# canSlaveV05b.net
KiCad netlist of a schematic drawn in EAGLE
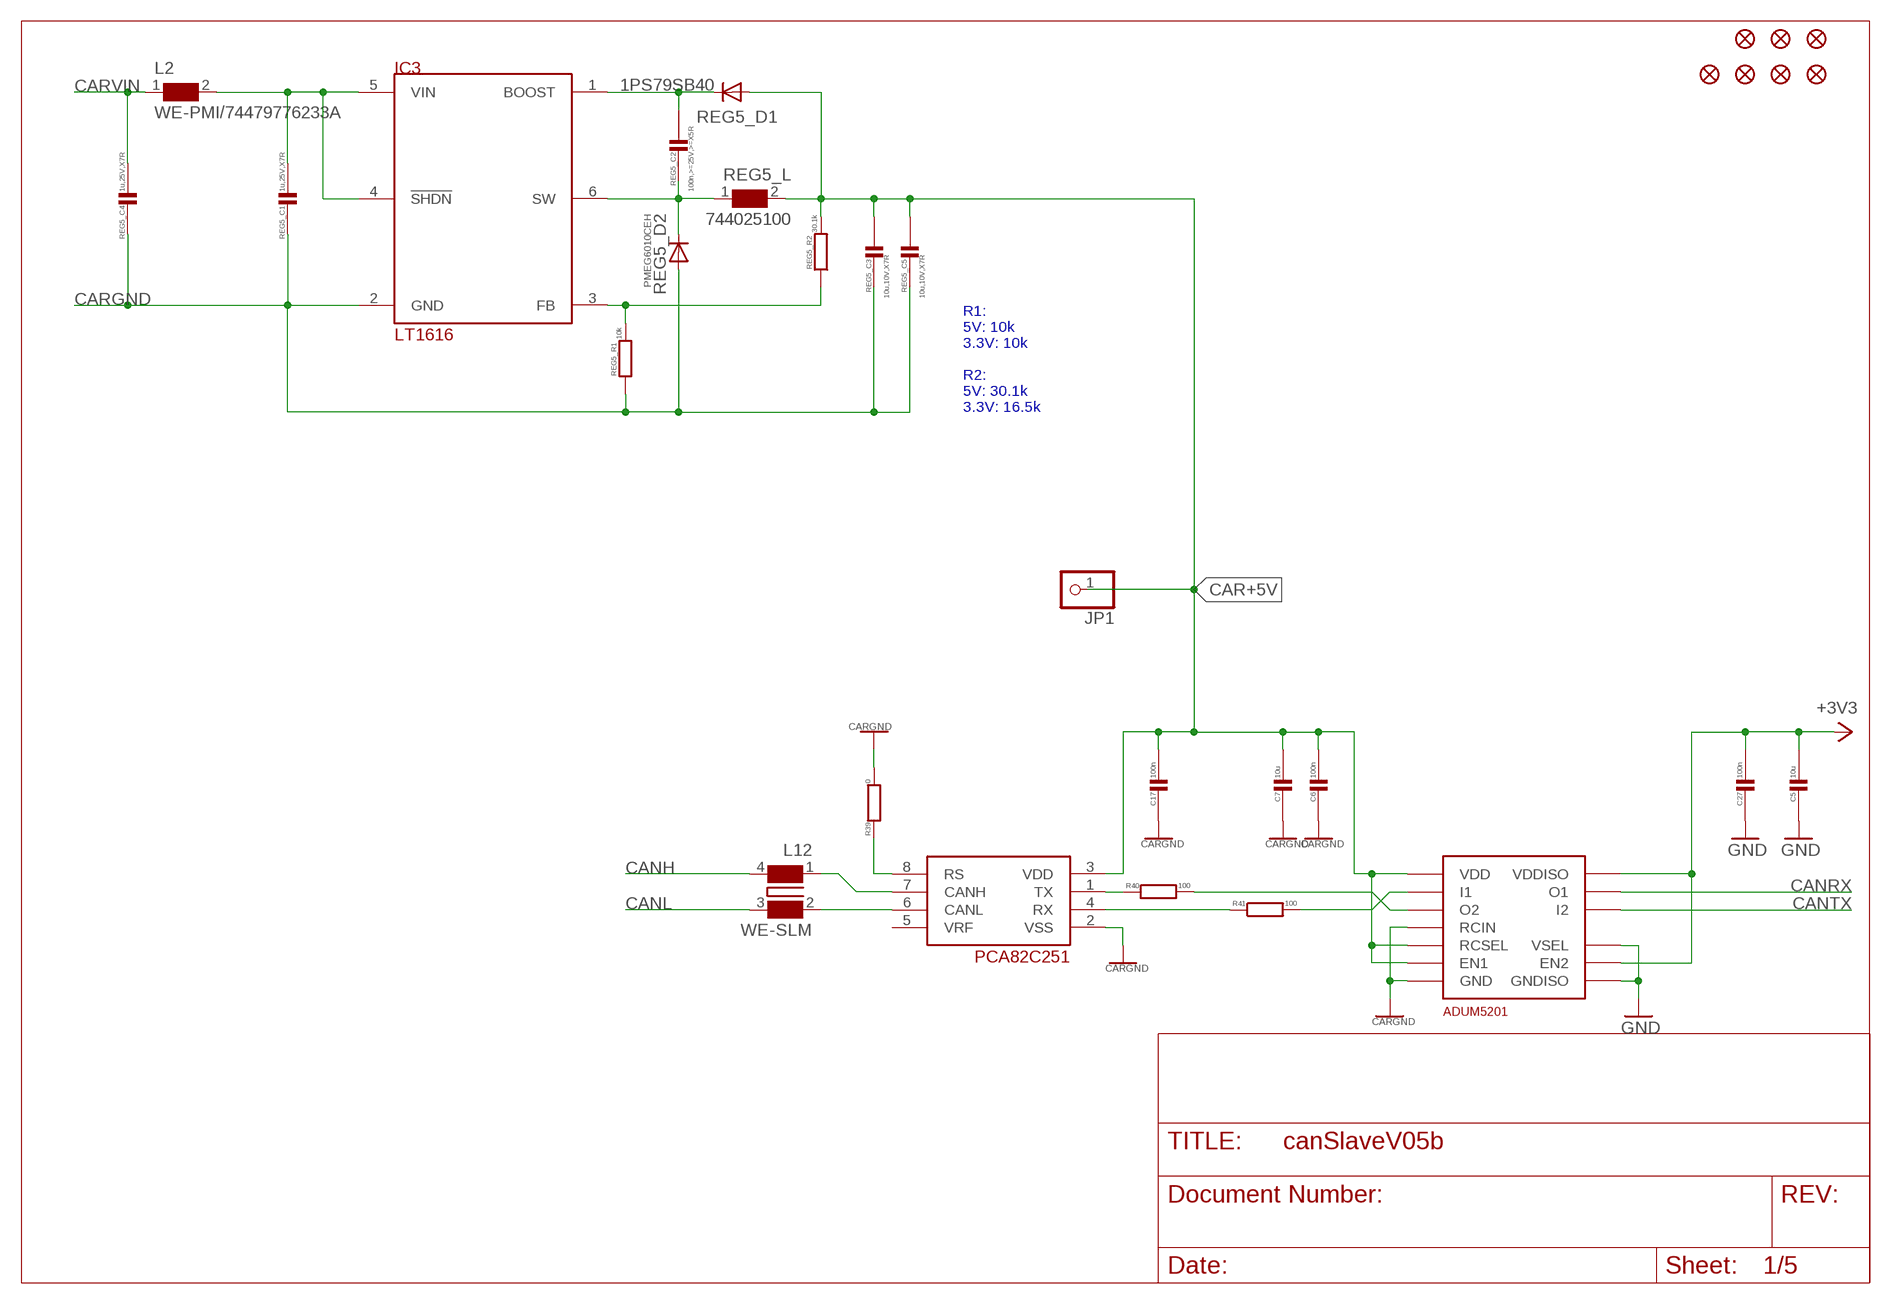
[diagram p0: schematic, sheet 1]
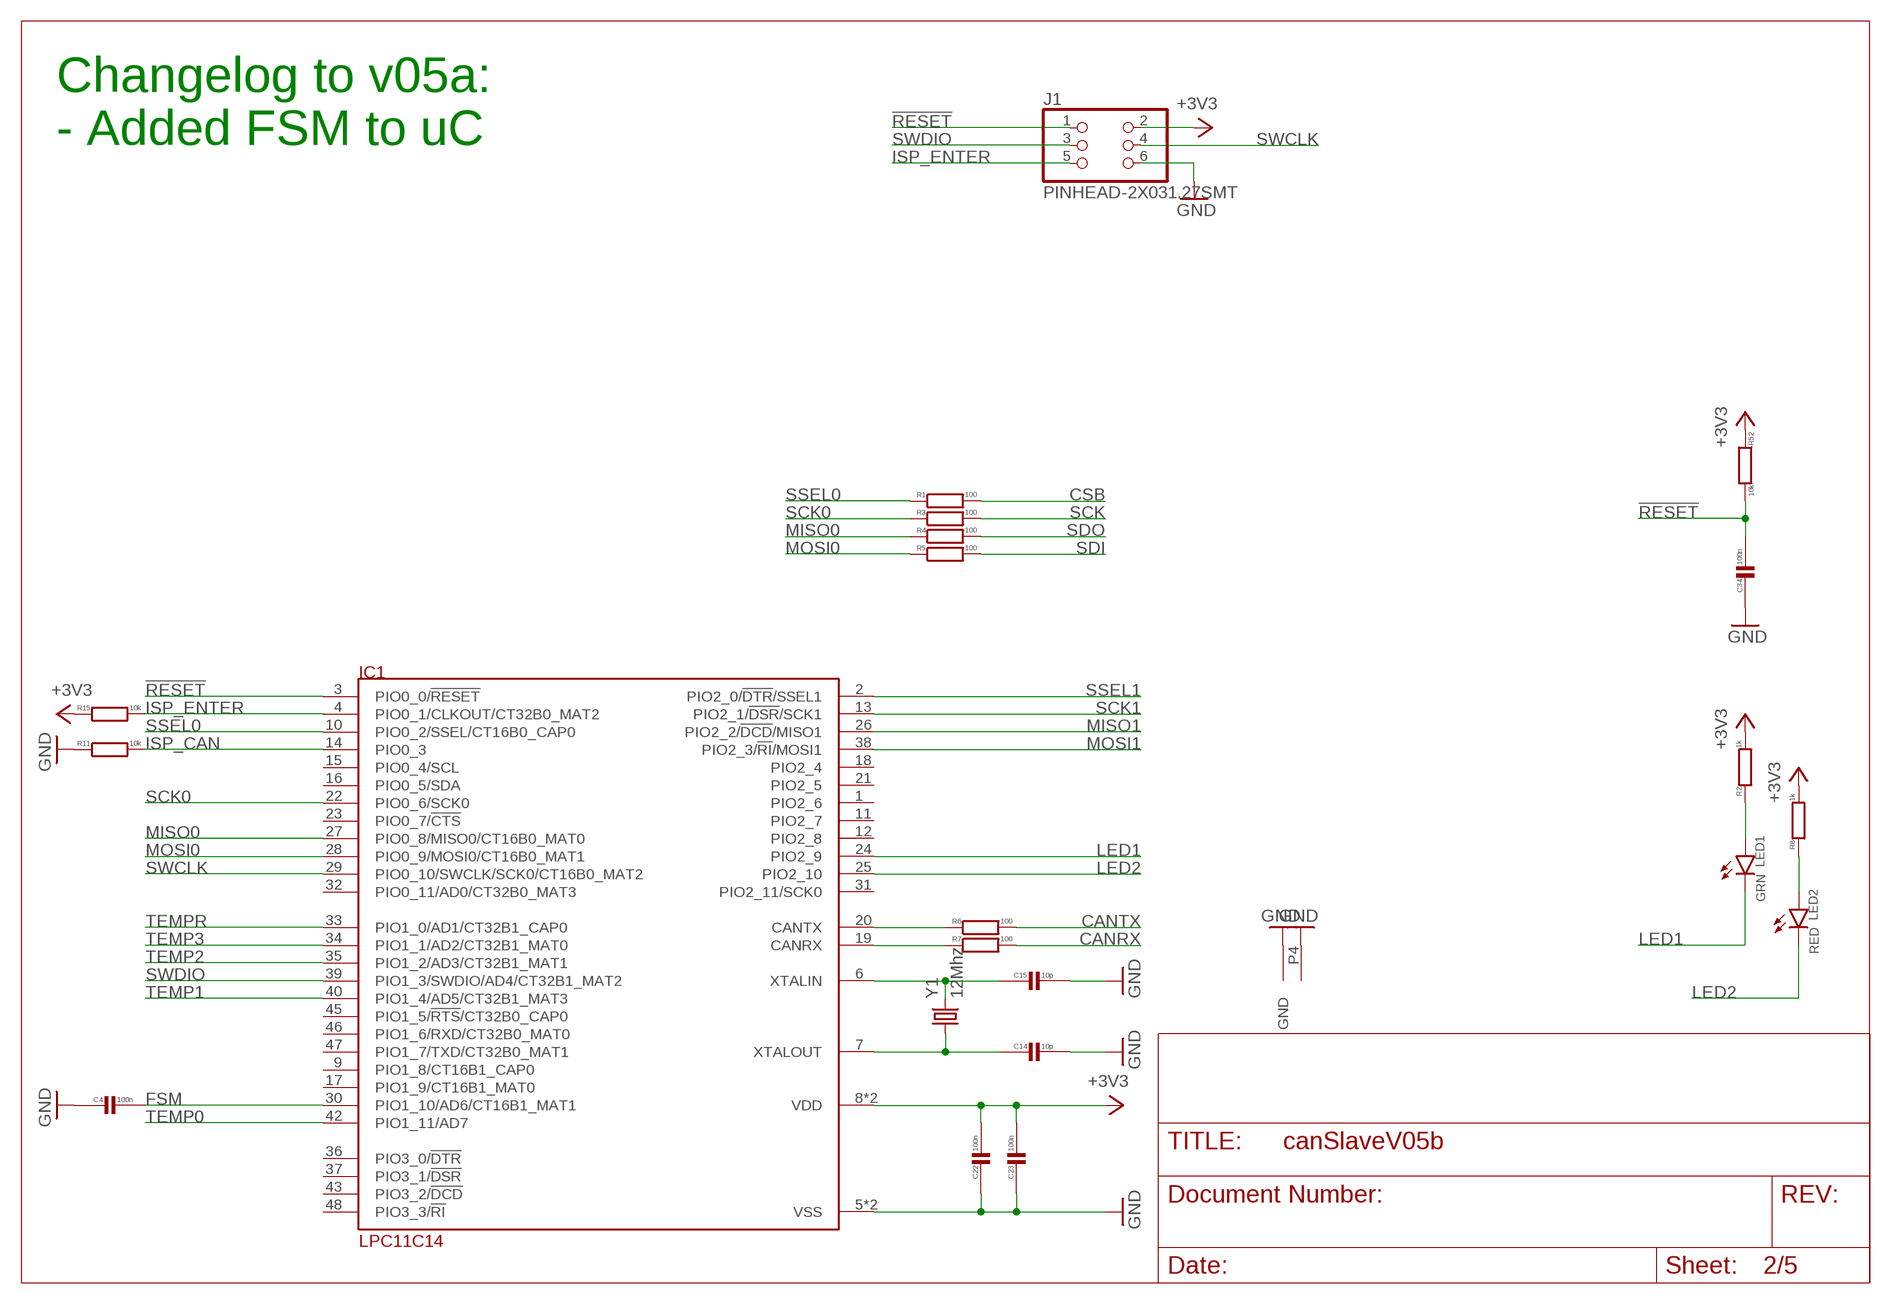
[diagram p1: schematic, sheet 2]
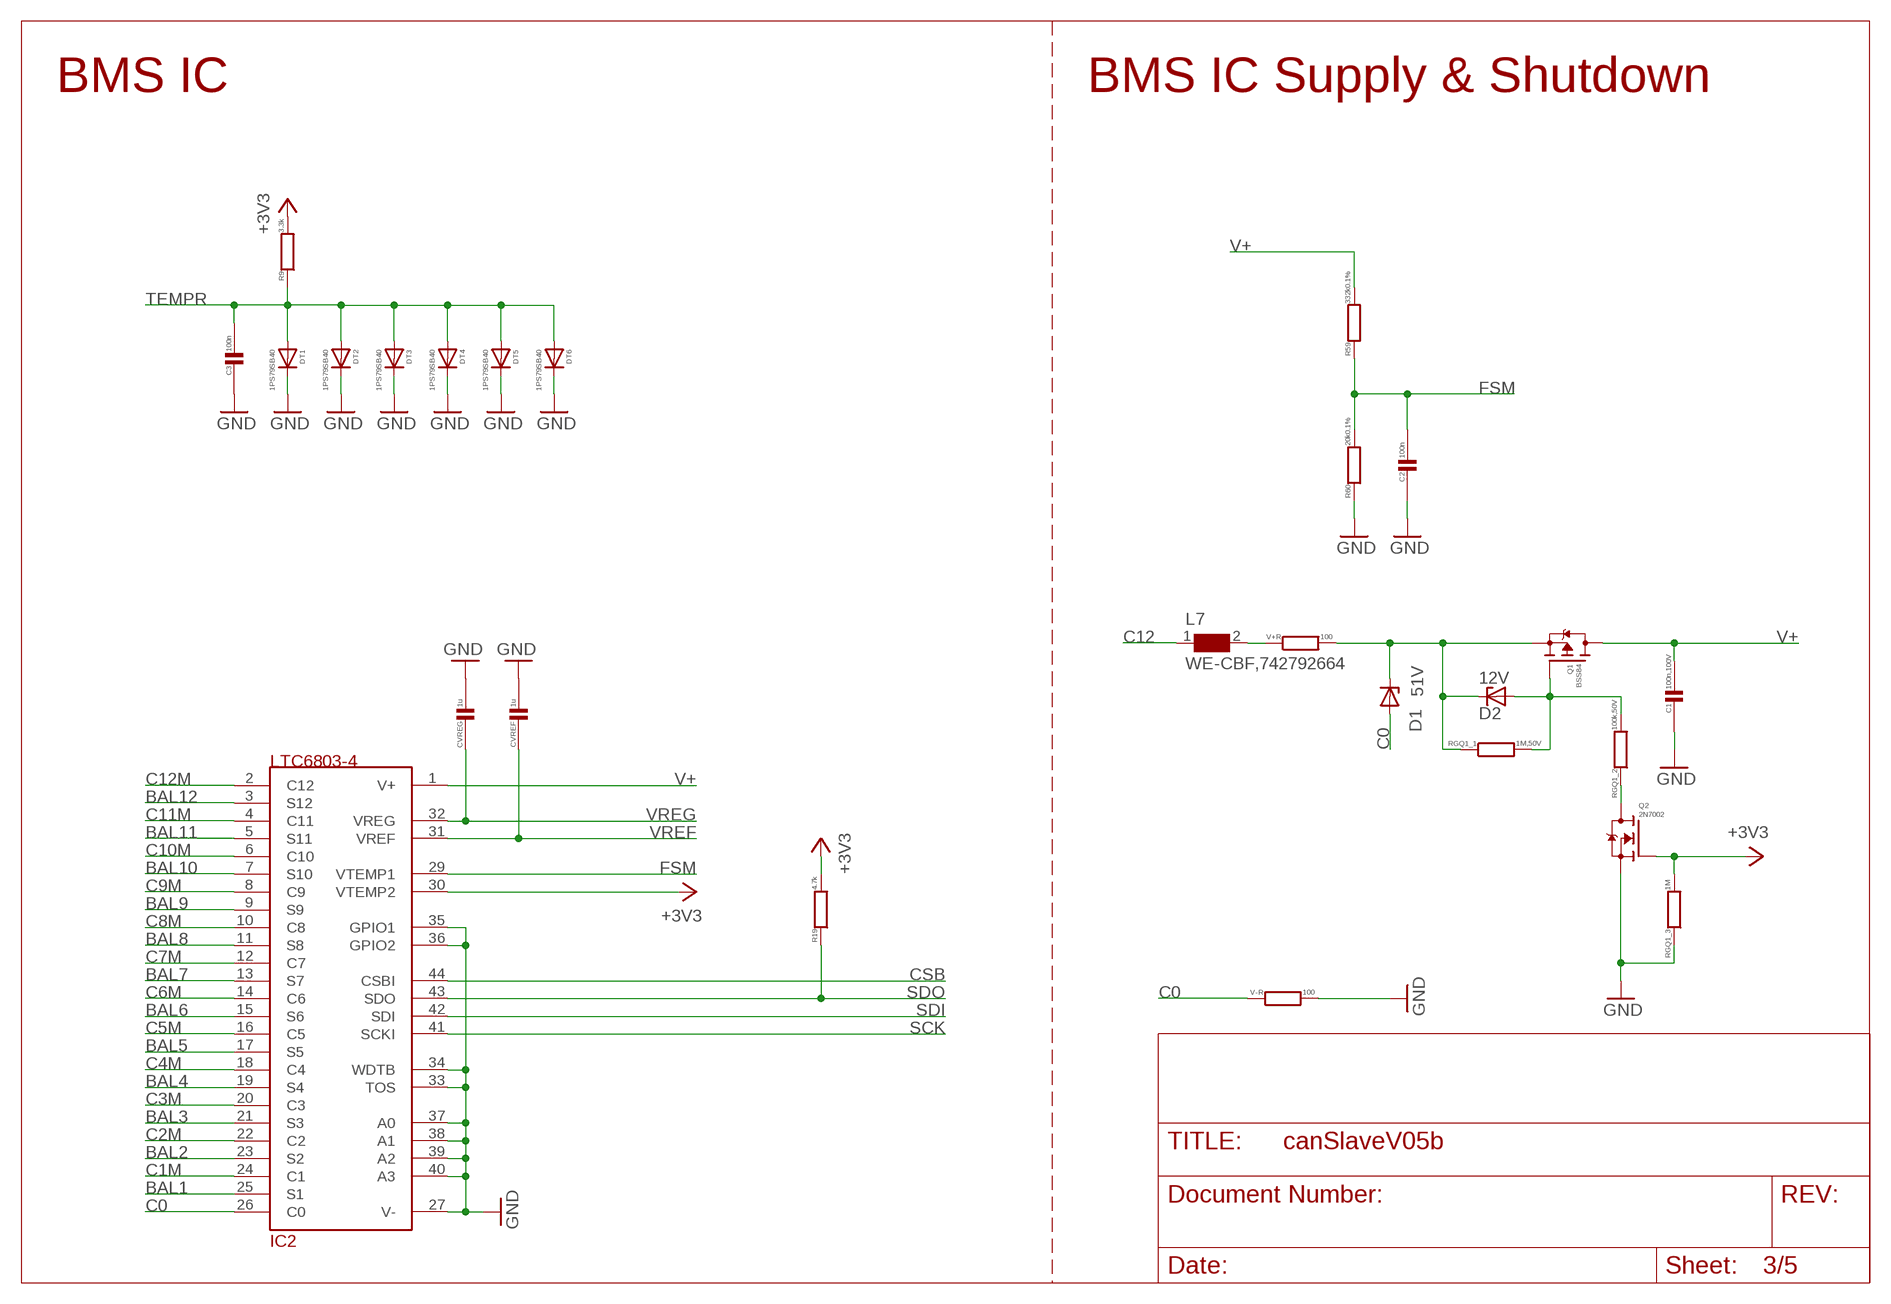
[diagram p2: schematic, sheet 3]
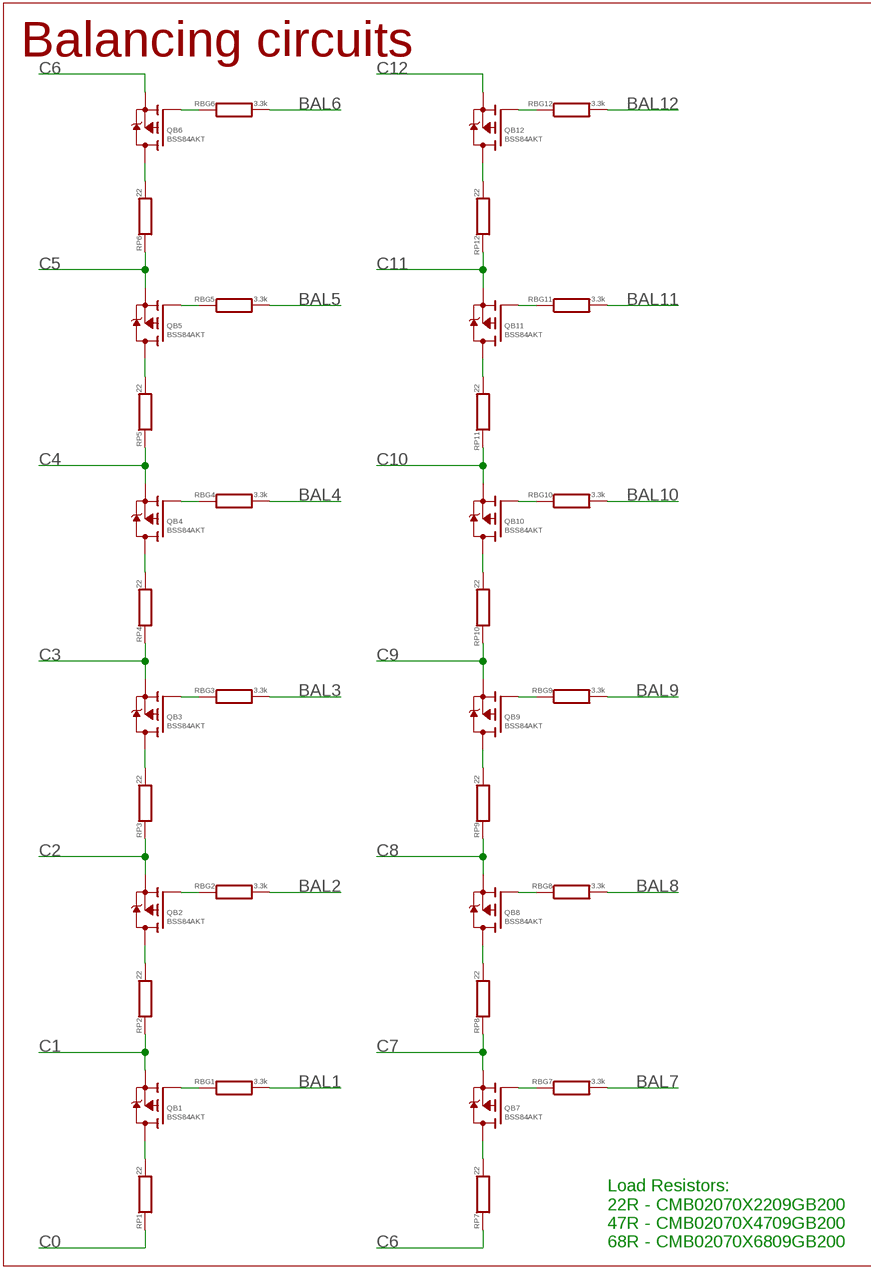
[diagram p3: schematic, sheet 4, part 1 of 2]
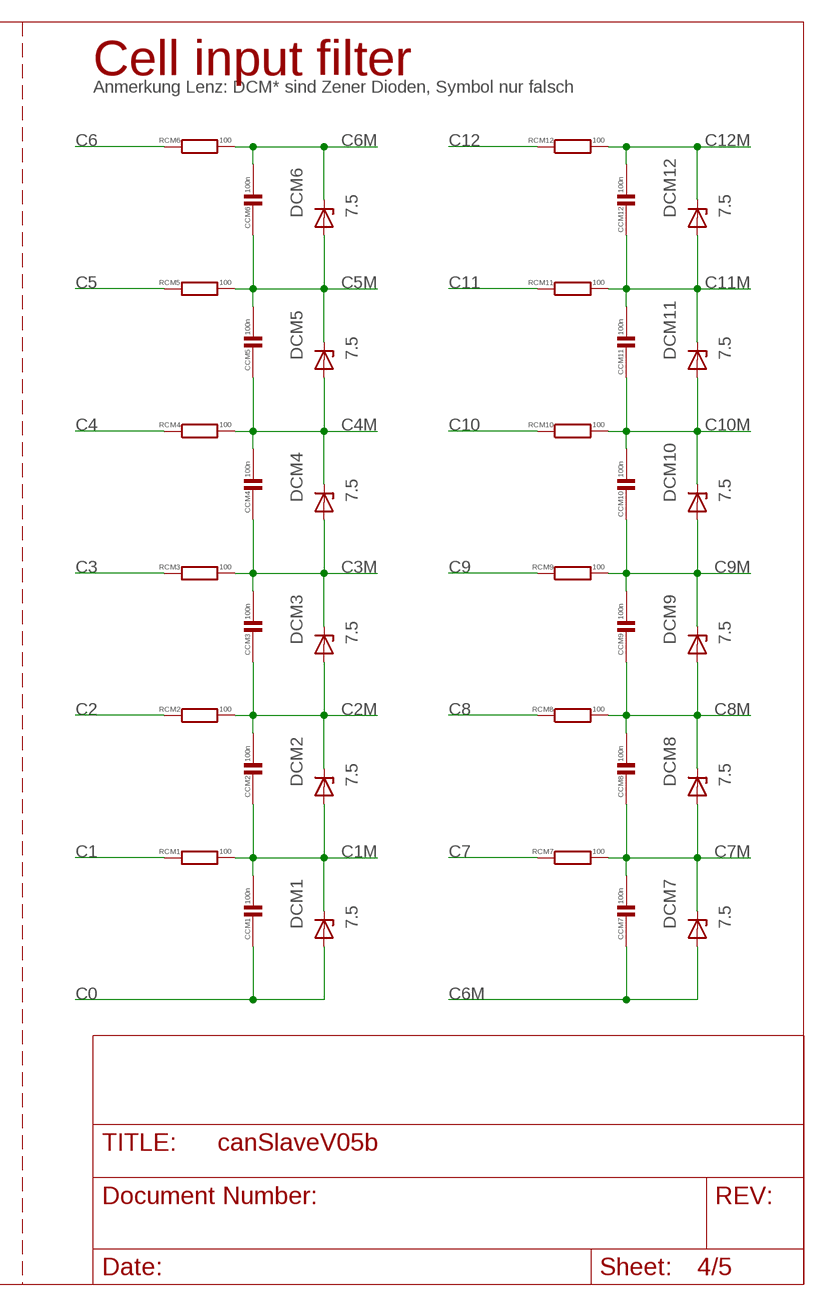
[diagram p4: schematic, sheet 4, part 2 of 2]
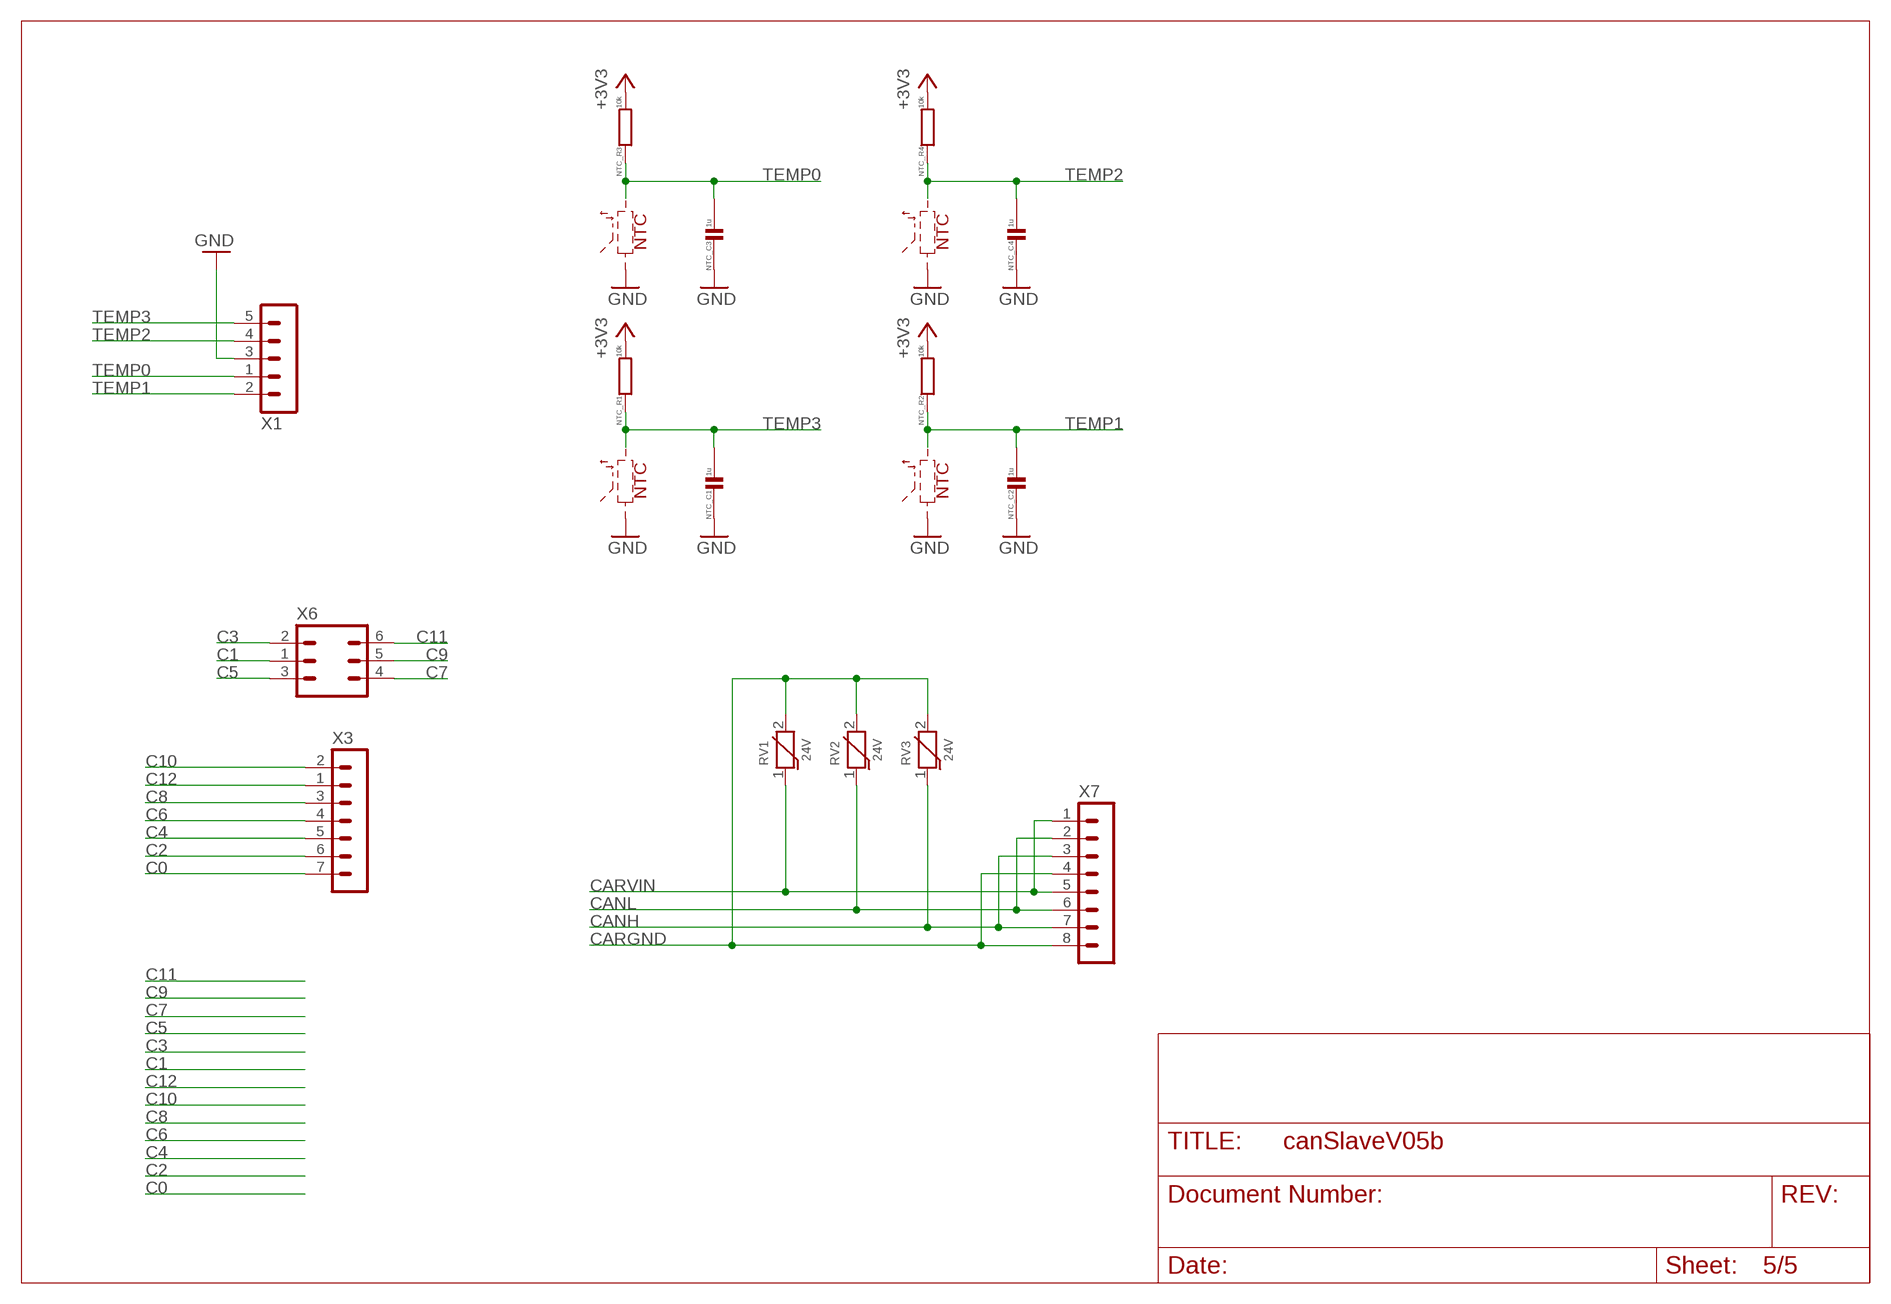
[diagram p5: schematic, sheet 5]

(export (version "E")
  (design (tool "Eeschema 10.0.6"))
  (components
    (comp (ref "NTC_C1")
      (value "1u")
      (footprint "eagle-import:C0402")
      (libsource (lib "eagle-import") (part "C0402"))
    )
    (comp (ref "NTC_C2")
      (value "1u")
      (footprint "eagle-import:C0402")
      (libsource (lib "eagle-import") (part "C0402"))
    )
    (comp (ref "NTC_C3")
      (value "1u")
      (footprint "eagle-import:C0402")
      (libsource (lib "eagle-import") (part "C0402"))
    )
    (comp (ref "NTC_C4")
      (value "1u")
      (footprint "eagle-import:C0402")
      (libsource (lib "eagle-import") (part "C0402"))
    )
    (comp (ref "NTC_R1")
      (value "10k")
      (footprint "eagle-import:R0402")
      (libsource (lib "eagle-import") (part "R0402"))
    )
    (comp (ref "NTC_R2")
      (value "10k")
      (footprint "eagle-import:R0402")
      (libsource (lib "eagle-import") (part "R0402"))
    )
    (comp (ref "NTC_R3")
      (value "10k")
      (footprint "eagle-import:R0402")
      (libsource (lib "eagle-import") (part "R0402"))
    )
    (comp (ref "NTC_R4")
      (value "10k")
      (footprint "eagle-import:R0402")
      (libsource (lib "eagle-import") (part "R0402"))
    )
    (comp (ref "RV1")
      (value "24V")
      (footprint "eagle-import:R0805")
      (libsource (lib "eagle-import") (part "VARISTOR0805"))
    )
    (comp (ref "RV2")
      (value "24V")
      (footprint "eagle-import:R0603")
      (libsource (lib "eagle-import") (part "VARISTOR0603"))
    )
    (comp (ref "RV3")
      (value "24V")
      (footprint "eagle-import:R0603")
      (libsource (lib "eagle-import") (part "VARISTOR0603"))
    )
    (comp (ref "X1")
      (value "HEADER_POS5_43650-0509")
      (footprint "eagle-import:43650-0509")
      (libsource (lib "eagle-import") (part "HEADER_POS5_?43650-0509"))
    )
    (comp (ref "X3")
      (value "HEADER_POS7_43650-0709")
      (footprint "eagle-import:43650-0709")
      (libsource (lib "eagle-import") (part "HEADER_POS7_?43650-0709"))
    )
    (comp (ref "X6")
      (value "HEADER_POS6_43650-0609")
      (footprint "eagle-import:43650-0609")
      (libsource (lib "eagle-import") (part "HEADER_POS6_?43650-0609"))
    )
    (comp (ref "X7")
      (value "HEADER_POS8_43045-0800")
      (footprint "eagle-import:43045-0800")
      (libsource (lib "eagle-import") (part "HEADER_POS8_?43045-0800"))
    )
    (comp (ref "C4")
      (value "100n")
      (footprint "eagle-import:C0402")
      (libsource (lib "eagle-import") (part "C0402"))
    )
    (comp (ref "C14")
      (value "10p")
      (footprint "eagle-import:C0402")
      (libsource (lib "eagle-import") (part "C0402"))
    )
    (comp (ref "C15")
      (value "10p")
      (footprint "eagle-import:C0402")
      (libsource (lib "eagle-import") (part "C0402"))
    )
    (comp (ref "C22")
      (value "100n")
      (footprint "eagle-import:C0402")
      (libsource (lib "eagle-import") (part "C0402"))
    )
    (comp (ref "C23")
      (value "100n")
      (footprint "eagle-import:C0402")
      (libsource (lib "eagle-import") (part "C0402"))
    )
    (comp (ref "C34")
      (value "100n")
      (footprint "eagle-import:C0402")
      (libsource (lib "eagle-import") (part "C0402"))
    )
    (comp (ref "IC1")
      (value "LPC11C14")
      (footprint "eagle-import:LQFP48")
      (libsource (lib "eagle-import") (part "LPC11C1X"))
    )
    (comp (ref "J1")
      (value "PINHEAD-2X031.27SMT")
      (footprint "eagle-import:2X03_1.27MM_SMT")
      (libsource (lib "eagle-import") (part "PINHEAD-2X031.27SMT"))
    )
    (comp (ref "LED1")
      (value "GRN")
      (footprint "eagle-import:CHIPLED_0603")
      (libsource (lib "eagle-import") (part "LED0603"))
    )
    (comp (ref "LED2")
      (value "RED")
      (footprint "eagle-import:CHIPLED_0603")
      (libsource (lib "eagle-import") (part "LED0603"))
    )
    (comp (ref "R1")
      (value "100")
      (footprint "eagle-import:R0402")
      (libsource (lib "eagle-import") (part "R0402"))
    )
    (comp (ref "R2")
      (value "1k")
      (footprint "eagle-import:R0402")
      (libsource (lib "eagle-import") (part "R0402"))
    )
    (comp (ref "R3")
      (value "100")
      (footprint "eagle-import:R0402")
      (libsource (lib "eagle-import") (part "R0402"))
    )
    (comp (ref "R4")
      (value "100")
      (footprint "eagle-import:R0402")
      (libsource (lib "eagle-import") (part "R0402"))
    )
    (comp (ref "R5")
      (value "100")
      (footprint "eagle-import:R0402")
      (libsource (lib "eagle-import") (part "R0402"))
    )
    (comp (ref "R6")
      (value "100")
      (footprint "eagle-import:R0402")
      (libsource (lib "eagle-import") (part "R0402"))
    )
    (comp (ref "R7")
      (value "100")
      (footprint "eagle-import:R0402")
      (libsource (lib "eagle-import") (part "R0402"))
    )
    (comp (ref "R8")
      (value "1k")
      (footprint "eagle-import:R0402")
      (libsource (lib "eagle-import") (part "R0402"))
    )
    (comp (ref "R11")
      (value "10k")
      (footprint "eagle-import:R0402")
      (libsource (lib "eagle-import") (part "R0402"))
    )
    (comp (ref "R15")
      (value "10k")
      (footprint "eagle-import:R0402")
      (libsource (lib "eagle-import") (part "R0402"))
    )
    (comp (ref "R52")
      (value "10k")
      (footprint "eagle-import:R0402")
      (libsource (lib "eagle-import") (part "R0402"))
    )
    (comp (ref "Y1")
      (value "12Mhz")
      (footprint "eagle-import:MT")
      (libsource (lib "eagle-import") (part "CRYSTAL43.2X2.5"))
    )
    (comp (ref "C1")
      (value "100n,100V")
      (footprint "eagle-import:C0603")
      (libsource (lib "eagle-import") (part "C0603"))
    )
    (comp (ref "C2")
      (value "100n")
      (footprint "eagle-import:C0402")
      (libsource (lib "eagle-import") (part "C0402"))
    )
    (comp (ref "C3")
      (value "100n")
      (footprint "eagle-import:C0402")
      (libsource (lib "eagle-import") (part "C0402"))
    )
    (comp (ref "CVREF")
      (value "1u")
      (footprint "eagle-import:C0402")
      (libsource (lib "eagle-import") (part "C0402"))
    )
    (comp (ref "CVREG")
      (value "1u")
      (footprint "eagle-import:C0402")
      (libsource (lib "eagle-import") (part "C0402"))
    )
    (comp (ref "D1")
      (value "51V")
      (footprint "eagle-import:SOD323-L")
      (libsource (lib "eagle-import") (part "ZENERSOD323"))
    )
    (comp (ref "D2")
      (value "12V")
      (footprint "eagle-import:SOD323-L")
      (libsource (lib "eagle-import") (part "ZENERSOD323"))
    )
    (comp (ref "DT1")
      (value "1PS79SB40")
      (footprint "eagle-import:SOD523")
      (libsource (lib "eagle-import") (part "DIODE-SOD523"))
    )
    (comp (ref "DT2")
      (value "1PS79SB40")
      (footprint "eagle-import:SOD523")
      (libsource (lib "eagle-import") (part "DIODE-SOD523"))
    )
    (comp (ref "DT3")
      (value "1PS79SB40")
      (footprint "eagle-import:SOD523")
      (libsource (lib "eagle-import") (part "DIODE-SOD523"))
    )
    (comp (ref "DT4")
      (value "1PS79SB40")
      (footprint "eagle-import:SOD523")
      (libsource (lib "eagle-import") (part "DIODE-SOD523"))
    )
    (comp (ref "DT5")
      (value "1PS79SB40")
      (footprint "eagle-import:SOD523")
      (libsource (lib "eagle-import") (part "DIODE-SOD523"))
    )
    (comp (ref "DT6")
      (value "1PS79SB40")
      (footprint "eagle-import:SOD523")
      (libsource (lib "eagle-import") (part "DIODE-SOD523"))
    )
    (comp (ref "IC2")
      (value "LTC6803-4")
      (footprint "eagle-import:44SSOP")
      (libsource (lib "eagle-import") (part "LTC6803-4"))
    )
    (comp (ref "L7")
      (value "WE-CBF,742792664")
      (footprint "eagle-import:0603")
      (libsource (lib "eagle-import") (part "WE-CBF_0603"))
    )
    (comp (ref "Q1")
      (value "BSS84")
      (footprint "eagle-import:SOT23")
      (libsource (lib "eagle-import") (part "BSS84"))
    )
    (comp (ref "Q2")
      (value "2N7002")
      (footprint "eagle-import:SOT23")
      (libsource (lib "eagle-import") (part "2N7002"))
    )
    (comp (ref "R9")
      (value "3.3k")
      (footprint "eagle-import:R0603")
      (libsource (lib "eagle-import") (part "R0603"))
    )
    (comp (ref "R19")
      (value "4.7k")
      (footprint "eagle-import:R0402")
      (libsource (lib "eagle-import") (part "R0402"))
    )
    (comp (ref "R59")
      (value "332k0.1%")
      (footprint "eagle-import:R0603")
      (libsource (lib "eagle-import") (part "R0603"))
    )
    (comp (ref "R60")
      (value "20k0.1%")
      (footprint "eagle-import:R0402")
      (libsource (lib "eagle-import") (part "R0402"))
    )
    (comp (ref "RGQ1_1")
      (value "1M,50V")
      (footprint "eagle-import:R0603")
      (libsource (lib "eagle-import") (part "R0603"))
    )
    (comp (ref "RGQ1_2")
      (value "100k,50V")
      (footprint "eagle-import:R0603")
      (libsource (lib "eagle-import") (part "R0603"))
    )
    (comp (ref "RGQ1_3")
      (value "1M")
      (footprint "eagle-import:R0402")
      (libsource (lib "eagle-import") (part "R0402"))
    )
    (comp (ref "V+R")
      (value "100")
      (footprint "eagle-import:R0603")
      (libsource (lib "eagle-import") (part "R0603"))
    )
    (comp (ref "V-R")
      (value "100")
      (footprint "eagle-import:R0603")
      (libsource (lib "eagle-import") (part "R0603"))
    )
    (comp (ref "CCM1")
      (value "100n")
      (footprint "eagle-import:C0402")
      (libsource (lib "eagle-import") (part "C0402"))
    )
    (comp (ref "CCM2")
      (value "100n")
      (footprint "eagle-import:C0402")
      (libsource (lib "eagle-import") (part "C0402"))
    )
    (comp (ref "CCM3")
      (value "100n")
      (footprint "eagle-import:C0402")
      (libsource (lib "eagle-import") (part "C0402"))
    )
    (comp (ref "CCM4")
      (value "100n")
      (footprint "eagle-import:C0402")
      (libsource (lib "eagle-import") (part "C0402"))
    )
    (comp (ref "CCM5")
      (value "100n")
      (footprint "eagle-import:C0402")
      (libsource (lib "eagle-import") (part "C0402"))
    )
    (comp (ref "CCM6")
      (value "100n")
      (footprint "eagle-import:C0402")
      (libsource (lib "eagle-import") (part "C0402"))
    )
    (comp (ref "CCM7")
      (value "100n")
      (footprint "eagle-import:C0402")
      (libsource (lib "eagle-import") (part "C0402"))
    )
    (comp (ref "CCM8")
      (value "100n")
      (footprint "eagle-import:C0402")
      (libsource (lib "eagle-import") (part "C0402"))
    )
    (comp (ref "CCM9")
      (value "100n")
      (footprint "eagle-import:C0402")
      (libsource (lib "eagle-import") (part "C0402"))
    )
    (comp (ref "CCM10")
      (value "100n")
      (footprint "eagle-import:C0402")
      (libsource (lib "eagle-import") (part "C0402"))
    )
    (comp (ref "CCM11")
      (value "100n")
      (footprint "eagle-import:C0402")
      (libsource (lib "eagle-import") (part "C0402"))
    )
    (comp (ref "CCM12")
      (value "100n")
      (footprint "eagle-import:C0402")
      (libsource (lib "eagle-import") (part "C0402"))
    )
    (comp (ref "DCM1")
      (value "7.5")
      (footprint "eagle-import:SOD523")
      (libsource (lib "eagle-import") (part "ZENERSOD523"))
    )
    (comp (ref "DCM2")
      (value "7.5")
      (footprint "eagle-import:SOD523")
      (libsource (lib "eagle-import") (part "ZENERSOD523"))
    )
    (comp (ref "DCM3")
      (value "7.5")
      (footprint "eagle-import:SOD523")
      (libsource (lib "eagle-import") (part "ZENERSOD523"))
    )
    (comp (ref "DCM4")
      (value "7.5")
      (footprint "eagle-import:SOD523")
      (libsource (lib "eagle-import") (part "ZENERSOD523"))
    )
    (comp (ref "DCM5")
      (value "7.5")
      (footprint "eagle-import:SOD523")
      (libsource (lib "eagle-import") (part "ZENERSOD523"))
    )
    (comp (ref "DCM6")
      (value "7.5")
      (footprint "eagle-import:SOD523")
      (libsource (lib "eagle-import") (part "ZENERSOD523"))
    )
    (comp (ref "DCM7")
      (value "7.5")
      (footprint "eagle-import:SOD523")
      (libsource (lib "eagle-import") (part "ZENERSOD523"))
    )
    (comp (ref "DCM8")
      (value "7.5")
      (footprint "eagle-import:SOD523")
      (libsource (lib "eagle-import") (part "ZENERSOD523"))
    )
    (comp (ref "DCM9")
      (value "7.5")
      (footprint "eagle-import:SOD523")
      (libsource (lib "eagle-import") (part "ZENERSOD523"))
    )
    (comp (ref "DCM10")
      (value "7.5")
      (footprint "eagle-import:SOD523")
      (libsource (lib "eagle-import") (part "ZENERSOD523"))
    )
    (comp (ref "DCM11")
      (value "7.5")
      (footprint "eagle-import:SOD523")
      (libsource (lib "eagle-import") (part "ZENERSOD523"))
    )
    (comp (ref "DCM12")
      (value "7.5")
      (footprint "eagle-import:SOD523")
      (libsource (lib "eagle-import") (part "ZENERSOD523"))
    )
    (comp (ref "QB1")
      (value "BSS84AKT")
      (footprint "eagle-import:SOT416")
      (libsource (lib "eagle-import") (part "BSS84AKT"))
    )
    (comp (ref "QB2")
      (value "BSS84AKT")
      (footprint "eagle-import:SOT416")
      (libsource (lib "eagle-import") (part "BSS84AKT"))
    )
    (comp (ref "QB3")
      (value "BSS84AKT")
      (footprint "eagle-import:SOT416")
      (libsource (lib "eagle-import") (part "BSS84AKT"))
    )
    (comp (ref "QB4")
      (value "BSS84AKT")
      (footprint "eagle-import:SOT416")
      (libsource (lib "eagle-import") (part "BSS84AKT"))
    )
    (comp (ref "QB5")
      (value "BSS84AKT")
      (footprint "eagle-import:SOT416")
      (libsource (lib "eagle-import") (part "BSS84AKT"))
    )
    (comp (ref "QB6")
      (value "BSS84AKT")
      (footprint "eagle-import:SOT416")
      (libsource (lib "eagle-import") (part "BSS84AKT"))
    )
    (comp (ref "QB7")
      (value "BSS84AKT")
      (footprint "eagle-import:SOT416")
      (libsource (lib "eagle-import") (part "BSS84AKT"))
    )
    (comp (ref "QB8")
      (value "BSS84AKT")
      (footprint "eagle-import:SOT416")
      (libsource (lib "eagle-import") (part "BSS84AKT"))
    )
    (comp (ref "QB9")
      (value "BSS84AKT")
      (footprint "eagle-import:SOT416")
      (libsource (lib "eagle-import") (part "BSS84AKT"))
    )
    (comp (ref "QB10")
      (value "BSS84AKT")
      (footprint "eagle-import:SOT416")
      (libsource (lib "eagle-import") (part "BSS84AKT"))
    )
    (comp (ref "QB11")
      (value "BSS84AKT")
      (footprint "eagle-import:SOT416")
      (libsource (lib "eagle-import") (part "BSS84AKT"))
    )
    (comp (ref "QB12")
      (value "BSS84AKT")
      (footprint "eagle-import:SOT416")
      (libsource (lib "eagle-import") (part "BSS84AKT"))
    )
    (comp (ref "RBG1")
      (value "3.3k")
      (footprint "eagle-import:R0402")
      (libsource (lib "eagle-import") (part "R0402"))
    )
    (comp (ref "RBG2")
      (value "3.3k")
      (footprint "eagle-import:R0402")
      (libsource (lib "eagle-import") (part "R0402"))
    )
    (comp (ref "RBG3")
      (value "3.3k")
      (footprint "eagle-import:R0402")
      (libsource (lib "eagle-import") (part "R0402"))
    )
    (comp (ref "RBG4")
      (value "3.3k")
      (footprint "eagle-import:R0402")
      (libsource (lib "eagle-import") (part "R0402"))
    )
    (comp (ref "RBG5")
      (value "3.3k")
      (footprint "eagle-import:R0402")
      (libsource (lib "eagle-import") (part "R0402"))
    )
    (comp (ref "RBG6")
      (value "3.3k")
      (footprint "eagle-import:R0402")
      (libsource (lib "eagle-import") (part "R0402"))
    )
    (comp (ref "RBG7")
      (value "3.3k")
      (footprint "eagle-import:R0402")
      (libsource (lib "eagle-import") (part "R0402"))
    )
    (comp (ref "RBG8")
      (value "3.3k")
      (footprint "eagle-import:R0402")
      (libsource (lib "eagle-import") (part "R0402"))
    )
    (comp (ref "RBG9")
      (value "3.3k")
      (footprint "eagle-import:R0402")
      (libsource (lib "eagle-import") (part "R0402"))
    )
    (comp (ref "RBG10")
      (value "3.3k")
      (footprint "eagle-import:R0402")
      (libsource (lib "eagle-import") (part "R0402"))
    )
    (comp (ref "RBG11")
      (value "3.3k")
      (footprint "eagle-import:R0402")
      (libsource (lib "eagle-import") (part "R0402"))
    )
    (comp (ref "RBG12")
      (value "3.3k")
      (footprint "eagle-import:R0402")
      (libsource (lib "eagle-import") (part "R0402"))
    )
    (comp (ref "RCM1")
      (value "100")
      (footprint "eagle-import:R0402")
      (libsource (lib "eagle-import") (part "R0402"))
    )
    (comp (ref "RCM2")
      (value "100")
      (footprint "eagle-import:R0402")
      (libsource (lib "eagle-import") (part "R0402"))
    )
    (comp (ref "RCM3")
      (value "100")
      (footprint "eagle-import:R0402")
      (libsource (lib "eagle-import") (part "R0402"))
    )
    (comp (ref "RCM4")
      (value "100")
      (footprint "eagle-import:R0402")
      (libsource (lib "eagle-import") (part "R0402"))
    )
    (comp (ref "RCM5")
      (value "100")
      (footprint "eagle-import:R0402")
      (libsource (lib "eagle-import") (part "R0402"))
    )
    (comp (ref "RCM6")
      (value "100")
      (footprint "eagle-import:R0402")
      (libsource (lib "eagle-import") (part "R0402"))
    )
    (comp (ref "RCM7")
      (value "100")
      (footprint "eagle-import:R0402")
      (libsource (lib "eagle-import") (part "R0402"))
    )
    (comp (ref "RCM8")
      (value "100")
      (footprint "eagle-import:R0402")
      (libsource (lib "eagle-import") (part "R0402"))
    )
    (comp (ref "RCM9")
      (value "100")
      (footprint "eagle-import:R0402")
      (libsource (lib "eagle-import") (part "R0402"))
    )
    (comp (ref "RCM10")
      (value "100")
      (footprint "eagle-import:R0402")
      (libsource (lib "eagle-import") (part "R0402"))
    )
    (comp (ref "RCM11")
      (value "100")
      (footprint "eagle-import:R0402")
      (libsource (lib "eagle-import") (part "R0402"))
    )
    (comp (ref "RCM12")
      (value "100")
      (footprint "eagle-import:R0402")
      (libsource (lib "eagle-import") (part "R0402"))
    )
    (comp (ref "RP1")
      (value "22")
      (footprint "eagle-import:MINI_MELF-0207R")
      (libsource (lib "eagle-import") (part "RMELF-0207R"))
    )
    (comp (ref "RP2")
      (value "22")
      (footprint "eagle-import:MINI_MELF-0207R")
      (libsource (lib "eagle-import") (part "RMELF-0207R"))
    )
    (comp (ref "RP3")
      (value "22")
      (footprint "eagle-import:MINI_MELF-0207R")
      (libsource (lib "eagle-import") (part "RMELF-0207R"))
    )
    (comp (ref "RP4")
      (value "22")
      (footprint "eagle-import:MINI_MELF-0207R")
      (libsource (lib "eagle-import") (part "RMELF-0207R"))
    )
    (comp (ref "RP5")
      (value "22")
      (footprint "eagle-import:MINI_MELF-0207R")
      (libsource (lib "eagle-import") (part "RMELF-0207R"))
    )
    (comp (ref "RP6")
      (value "22")
      (footprint "eagle-import:MINI_MELF-0207R")
      (libsource (lib "eagle-import") (part "RMELF-0207R"))
    )
    (comp (ref "RP7")
      (value "22")
      (footprint "eagle-import:MINI_MELF-0207R")
      (libsource (lib "eagle-import") (part "RMELF-0207R"))
    )
    (comp (ref "RP8")
      (value "22")
      (footprint "eagle-import:MINI_MELF-0207R")
      (libsource (lib "eagle-import") (part "RMELF-0207R"))
    )
    (comp (ref "RP9")
      (value "22")
      (footprint "eagle-import:MINI_MELF-0207R")
      (libsource (lib "eagle-import") (part "RMELF-0207R"))
    )
    (comp (ref "RP10")
      (value "22")
      (footprint "eagle-import:MINI_MELF-0207R")
      (libsource (lib "eagle-import") (part "RMELF-0207R"))
    )
    (comp (ref "RP11")
      (value "22")
      (footprint "eagle-import:MINI_MELF-0207R")
      (libsource (lib "eagle-import") (part "RMELF-0207R"))
    )
    (comp (ref "RP12")
      (value "22")
      (footprint "eagle-import:MINI_MELF-0207R")
      (libsource (lib "eagle-import") (part "RMELF-0207R"))
    )
    (comp (ref "C5")
      (value "10u")
      (footprint "eagle-import:C0603")
      (libsource (lib "eagle-import") (part "C0603"))
    )
    (comp (ref "C6")
      (value "100n")
      (footprint "eagle-import:C0402")
      (libsource (lib "eagle-import") (part "C0402"))
    )
    (comp (ref "C7")
      (value "10u")
      (footprint "eagle-import:C0603")
      (libsource (lib "eagle-import") (part "C0603"))
    )
    (comp (ref "C17")
      (value "100n")
      (footprint "eagle-import:C0402")
      (libsource (lib "eagle-import") (part "C0402"))
    )
    (comp (ref "C27")
      (value "100n")
      (footprint "eagle-import:C0402")
      (libsource (lib "eagle-import") (part "C0402"))
    )
    (comp (ref "FID2")
      (value "FIDUCIAL\"\"")
      (footprint "eagle-import:FIDUCIAL_1MM")
      (libsource (lib "eagle-import") (part "FIDUCIAL{dblquote}{dblquote}"))
    )
    (comp (ref "FID3")
      (value "FIDUCIAL\"\"")
      (footprint "eagle-import:FIDUCIAL_1MM")
      (libsource (lib "eagle-import") (part "FIDUCIAL{dblquote}{dblquote}"))
    )
    (comp (ref "FID4")
      (value "FIDUCIAL\"\"")
      (footprint "eagle-import:FIDUCIAL_1MM")
      (libsource (lib "eagle-import") (part "FIDUCIAL{dblquote}{dblquote}"))
    )
    (comp (ref "FID7")
      (value "FIDUCIAL\"\"")
      (footprint "eagle-import:FIDUCIAL_1MM")
      (libsource (lib "eagle-import") (part "FIDUCIAL{dblquote}{dblquote}"))
    )
    (comp (ref "FID8")
      (value "FIDUCIAL\"\"")
      (footprint "eagle-import:FIDUCIAL_1MM")
      (libsource (lib "eagle-import") (part "FIDUCIAL{dblquote}{dblquote}"))
    )
    (comp (ref "FID9")
      (value "FIDUCIAL\"\"")
      (footprint "eagle-import:FIDUCIAL_1MM")
      (libsource (lib "eagle-import") (part "FIDUCIAL{dblquote}{dblquote}"))
    )
    (comp (ref "FID10")
      (value "FIDUCIAL\"\"")
      (footprint "eagle-import:FIDUCIAL_1MM")
      (libsource (lib "eagle-import") (part "FIDUCIAL{dblquote}{dblquote}"))
    )
    (comp (ref "IC3")
      (value "LT1616")
      (footprint "eagle-import:SOT23-6")
      (libsource (lib "eagle-import") (part "LT1616"))
    )
    (comp (ref "IC5")
      (value "PCA82C251")
      (footprint "eagle-import:SO-8")
      (libsource (lib "eagle-import") (part "MCP2551"))
    )
    (comp (ref "JP1")
      (value "PINHD-1X1")
      (footprint "eagle-import:1X01")
      (libsource (lib "eagle-import") (part "PINHD-1X1"))
    )
    (comp (ref "L2")
      (value "WE-PMI/74479776233A")
      (footprint "eagle-import:WE-PMI_0806")
      (libsource (lib "eagle-import") (part "WE-PMI_0806"))
    )
    (comp (ref "L12")
      (value "WE-SLM")
      (footprint "eagle-import:WE-SLM")
      (libsource (lib "eagle-import") (part "WE-SLM"))
    )
    (comp (ref "R39")
      (value "0")
      (footprint "eagle-import:R0402")
      (libsource (lib "eagle-import") (part "R0402"))
    )
    (comp (ref "R40")
      (value "100")
      (footprint "eagle-import:R0402")
      (libsource (lib "eagle-import") (part "R0402"))
    )
    (comp (ref "R41")
      (value "100")
      (footprint "eagle-import:R0402")
      (libsource (lib "eagle-import") (part "R0402"))
    )
    (comp (ref "REG5_C1")
      (value "1u,25V,X7R")
      (footprint "eagle-import:C0805")
      (libsource (lib "eagle-import") (part "C0805"))
    )
    (comp (ref "REG5_C2")
      (value "100n,>=25V,>=X5R")
      (footprint "eagle-import:C0402")
      (libsource (lib "eagle-import") (part "C0402"))
    )
    (comp (ref "REG5_C3")
      (value "10u,10V,X7R")
      (footprint "eagle-import:C0805")
      (libsource (lib "eagle-import") (part "C0805"))
    )
    (comp (ref "REG5_C4")
      (value "1u,25V,X7R")
      (footprint "eagle-import:C0805")
      (libsource (lib "eagle-import") (part "C0805"))
    )
    (comp (ref "REG5_C5")
      (value "10u,10V,X7R")
      (footprint "eagle-import:C0805")
      (libsource (lib "eagle-import") (part "C0805"))
    )
    (comp (ref "REG5_D1")
      (value "1PS79SB40")
      (footprint "eagle-import:SOD523")
      (libsource (lib "eagle-import") (part "DIODE-SOD523"))
    )
    (comp (ref "REG5_D2")
      (value "PMEG6010CEH")
      (footprint "eagle-import:SOD123")
      (libsource (lib "eagle-import") (part "D-SOD123"))
    )
    (comp (ref "REG5_L")
      (value "744025100")
      (footprint "eagle-import:WE-TPC_2828")
      (libsource (lib "eagle-import") (part "WE-TPC_2828"))
    )
    (comp (ref "REG5_R1")
      (value "10k")
      (footprint "eagle-import:R0402")
      (libsource (lib "eagle-import") (part "R0402"))
    )
    (comp (ref "REG5_R2")
      (value "30.1k")
      (footprint "eagle-import:R0402")
      (libsource (lib "eagle-import") (part "R0402"))
    )
    (comp (ref "U$2")
      (value "ADUM5201")
      (footprint "eagle-import:SO16WB")
      (libsource (lib "eagle-import") (part "ADUM5201"))
    )
  )
  (nets
    (net (code "1") (name "+3V3") (class "Default")
      (node (ref "C22") (pin "1") (pinfunction "1_1") (pintype "passive"))
      (node (ref "C23") (pin "1") (pinfunction "1_1") (pintype "passive"))
      (node (ref "C27") (pin "1") (pinfunction "1_1") (pintype "passive"))
      (node (ref "C5") (pin "1") (pinfunction "1_1") (pintype "passive"))
      (node (ref "IC1") (pin "44") (pinfunction "VDD_44") (pintype "bidirectional"))
      (node (ref "IC1") (pin "8") (pinfunction "VDD_8") (pintype "bidirectional"))
      (node (ref "IC2") (pin "30") (pinfunction "VTEMP2_30") (pintype "bidirectional"))
      (node (ref "J1") (pin "2") (pinfunction "2_2") (pintype "passive"))
      (node (ref "NTC_R1") (pin "2") (pinfunction "2_2") (pintype "passive"))
      (node (ref "NTC_R2") (pin "2") (pinfunction "2_2") (pintype "passive"))
      (node (ref "NTC_R3") (pin "2") (pinfunction "2_2") (pintype "passive"))
      (node (ref "NTC_R4") (pin "2") (pinfunction "2_2") (pintype "passive"))
      (node (ref "Q2") (pin "1") (pinfunction "G_1") (pintype "passive"))
      (node (ref "R15") (pin "1") (pinfunction "1_1") (pintype "passive"))
      (node (ref "R19") (pin "2") (pinfunction "2_2") (pintype "passive"))
      (node (ref "R2") (pin "2") (pinfunction "2_2") (pintype "passive"))
      (node (ref "R52") (pin "1") (pinfunction "1_1") (pintype "passive"))
      (node (ref "R8") (pin "2") (pinfunction "2_2") (pintype "passive"))
      (node (ref "R9") (pin "2") (pinfunction "2_2") (pintype "passive"))
      (node (ref "RGQ1_3") (pin "2") (pinfunction "2_2") (pintype "passive"))
      (node (ref "U$2") (pin "P$10") (pinfunction "EN2_P$10") (pintype "bidirectional"))
      (node (ref "U$2") (pin "P$16") (pinfunction "VDDISO_P$16") (pintype "bidirectional"))
    )
    (net (code "2") (name "BAL1") (class "Default")
      (node (ref "IC2") (pin "25") (pinfunction "S1_25") (pintype "bidirectional"))
      (node (ref "RBG1") (pin "2") (pinfunction "2_2") (pintype "passive"))
    )
    (net (code "3") (name "BAL2") (class "Default")
      (node (ref "IC2") (pin "23") (pinfunction "S2_23") (pintype "bidirectional"))
      (node (ref "RBG2") (pin "2") (pinfunction "2_2") (pintype "passive"))
    )
    (net (code "4") (name "BAL3") (class "Default")
      (node (ref "IC2") (pin "21") (pinfunction "S3_21") (pintype "bidirectional"))
      (node (ref "RBG3") (pin "2") (pinfunction "2_2") (pintype "passive"))
    )
    (net (code "5") (name "BAL4") (class "Default")
      (node (ref "IC2") (pin "19") (pinfunction "S4_19") (pintype "bidirectional"))
      (node (ref "RBG4") (pin "2") (pinfunction "2_2") (pintype "passive"))
    )
    (net (code "6") (name "BAL5") (class "Default")
      (node (ref "IC2") (pin "17") (pinfunction "S5_17") (pintype "bidirectional"))
      (node (ref "RBG5") (pin "2") (pinfunction "2_2") (pintype "passive"))
    )
    (net (code "7") (name "BAL6") (class "Default")
      (node (ref "IC2") (pin "15") (pinfunction "S6_15") (pintype "bidirectional"))
      (node (ref "RBG6") (pin "2") (pinfunction "2_2") (pintype "passive"))
    )
    (net (code "8") (name "BAL7") (class "Default")
      (node (ref "IC2") (pin "13") (pinfunction "S7_13") (pintype "bidirectional"))
      (node (ref "RBG7") (pin "2") (pinfunction "2_2") (pintype "passive"))
    )
    (net (code "9") (name "BAL8") (class "Default")
      (node (ref "IC2") (pin "11") (pinfunction "S8_11") (pintype "bidirectional"))
      (node (ref "RBG8") (pin "2") (pinfunction "2_2") (pintype "passive"))
    )
    (net (code "10") (name "BAL9") (class "Default")
      (node (ref "IC2") (pin "9") (pinfunction "S9_9") (pintype "bidirectional"))
      (node (ref "RBG9") (pin "2") (pinfunction "2_2") (pintype "passive"))
    )
    (net (code "11") (name "BAL10") (class "Default")
      (node (ref "IC2") (pin "7") (pinfunction "S10_7") (pintype "bidirectional"))
      (node (ref "RBG10") (pin "2") (pinfunction "2_2") (pintype "passive"))
    )
    (net (code "12") (name "BAL11") (class "Default")
      (node (ref "IC2") (pin "5") (pinfunction "S11_5") (pintype "bidirectional"))
      (node (ref "RBG11") (pin "2") (pinfunction "2_2") (pintype "passive"))
    )
    (net (code "13") (name "BAL12") (class "Default")
      (node (ref "IC2") (pin "3") (pinfunction "S12_3") (pintype "bidirectional"))
      (node (ref "RBG12") (pin "2") (pinfunction "2_2") (pintype "passive"))
    )
    (net (code "14") (name "C0") (class "Default")
      (node (ref "CCM1") (pin "2") (pinfunction "2_2") (pintype "passive"))
      (node (ref "D1") (pin "A") (pinfunction "A_A") (pintype "passive"))
      (node (ref "DCM1") (pin "A") (pinfunction "A_A") (pintype "passive"))
      (node (ref "IC2") (pin "26") (pinfunction "C0_26") (pintype "bidirectional"))
      (node (ref "RP1") (pin "1") (pinfunction "1_1") (pintype "passive"))
      (node (ref "V-R") (pin "1") (pinfunction "1_1") (pintype "passive"))
      (node (ref "X3") (pin "7") (pinfunction "7_7") (pintype "passive"))
    )
    (net (code "15") (name "C1") (class "Default")
      (node (ref "QB1") (pin "2") (pinfunction "S_2") (pintype "passive"))
      (node (ref "RCM1") (pin "1") (pinfunction "1_1") (pintype "passive"))
      (node (ref "RP2") (pin "1") (pinfunction "1_1") (pintype "passive"))
      (node (ref "X6") (pin "1") (pinfunction "2_1") (pintype "passive"))
    )
    (net (code "16") (name "C1M") (class "Default")
      (node (ref "CCM1") (pin "1") (pinfunction "1_1") (pintype "passive"))
      (node (ref "CCM2") (pin "2") (pinfunction "2_2") (pintype "passive"))
      (node (ref "DCM1") (pin "C") (pinfunction "C_C") (pintype "passive"))
      (node (ref "DCM2") (pin "A") (pinfunction "A_A") (pintype "passive"))
      (node (ref "IC2") (pin "24") (pinfunction "C1_24") (pintype "bidirectional"))
      (node (ref "RCM1") (pin "2") (pinfunction "2_2") (pintype "passive"))
    )
    (net (code "17") (name "C2") (class "Default")
      (node (ref "QB2") (pin "2") (pinfunction "S_2") (pintype "passive"))
      (node (ref "RCM2") (pin "1") (pinfunction "1_1") (pintype "passive"))
      (node (ref "RP3") (pin "1") (pinfunction "1_1") (pintype "passive"))
      (node (ref "X3") (pin "6") (pinfunction "6_6") (pintype "passive"))
    )
    (net (code "18") (name "C2M") (class "Default")
      (node (ref "CCM2") (pin "1") (pinfunction "1_1") (pintype "passive"))
      (node (ref "CCM3") (pin "2") (pinfunction "2_2") (pintype "passive"))
      (node (ref "DCM2") (pin "C") (pinfunction "C_C") (pintype "passive"))
      (node (ref "DCM3") (pin "A") (pinfunction "A_A") (pintype "passive"))
      (node (ref "IC2") (pin "22") (pinfunction "C2_22") (pintype "bidirectional"))
      (node (ref "RCM2") (pin "2") (pinfunction "2_2") (pintype "passive"))
    )
    (net (code "19") (name "C3") (class "Default")
      (node (ref "QB3") (pin "2") (pinfunction "S_2") (pintype "passive"))
      (node (ref "RCM3") (pin "1") (pinfunction "1_1") (pintype "passive"))
      (node (ref "RP4") (pin "1") (pinfunction "1_1") (pintype "passive"))
      (node (ref "X6") (pin "2") (pinfunction "1_2") (pintype "passive"))
    )
    (net (code "20") (name "C3M") (class "Default")
      (node (ref "CCM3") (pin "1") (pinfunction "1_1") (pintype "passive"))
      (node (ref "CCM4") (pin "2") (pinfunction "2_2") (pintype "passive"))
      (node (ref "DCM3") (pin "C") (pinfunction "C_C") (pintype "passive"))
      (node (ref "DCM4") (pin "A") (pinfunction "A_A") (pintype "passive"))
      (node (ref "IC2") (pin "20") (pinfunction "C3_20") (pintype "bidirectional"))
      (node (ref "RCM3") (pin "2") (pinfunction "2_2") (pintype "passive"))
    )
    (net (code "21") (name "C4") (class "Default")
      (node (ref "QB4") (pin "2") (pinfunction "S_2") (pintype "passive"))
      (node (ref "RCM4") (pin "1") (pinfunction "1_1") (pintype "passive"))
      (node (ref "RP5") (pin "1") (pinfunction "1_1") (pintype "passive"))
      (node (ref "X3") (pin "5") (pinfunction "5_5") (pintype "passive"))
    )
    (net (code "22") (name "C4M") (class "Default")
      (node (ref "CCM4") (pin "1") (pinfunction "1_1") (pintype "passive"))
      (node (ref "CCM5") (pin "2") (pinfunction "2_2") (pintype "passive"))
      (node (ref "DCM4") (pin "C") (pinfunction "C_C") (pintype "passive"))
      (node (ref "DCM5") (pin "A") (pinfunction "A_A") (pintype "passive"))
      (node (ref "IC2") (pin "18") (pinfunction "C4_18") (pintype "bidirectional"))
      (node (ref "RCM4") (pin "2") (pinfunction "2_2") (pintype "passive"))
    )
    (net (code "23") (name "C5") (class "Default")
      (node (ref "QB5") (pin "2") (pinfunction "S_2") (pintype "passive"))
      (node (ref "RCM5") (pin "1") (pinfunction "1_1") (pintype "passive"))
      (node (ref "RP6") (pin "1") (pinfunction "1_1") (pintype "passive"))
      (node (ref "X6") (pin "3") (pinfunction "3_3") (pintype "passive"))
    )
    (net (code "24") (name "C5M") (class "Default")
      (node (ref "CCM5") (pin "1") (pinfunction "1_1") (pintype "passive"))
      (node (ref "CCM6") (pin "2") (pinfunction "2_2") (pintype "passive"))
      (node (ref "DCM5") (pin "C") (pinfunction "C_C") (pintype "passive"))
      (node (ref "DCM6") (pin "A") (pinfunction "A_A") (pintype "passive"))
      (node (ref "IC2") (pin "16") (pinfunction "C5_16") (pintype "bidirectional"))
      (node (ref "RCM5") (pin "2") (pinfunction "2_2") (pintype "passive"))
    )
    (net (code "25") (name "C6") (class "Default")
      (node (ref "QB6") (pin "2") (pinfunction "S_2") (pintype "passive"))
      (node (ref "RCM6") (pin "1") (pinfunction "1_1") (pintype "passive"))
      (node (ref "RP7") (pin "1") (pinfunction "1_1") (pintype "passive"))
      (node (ref "X3") (pin "4") (pinfunction "4_4") (pintype "passive"))
    )
    (net (code "26") (name "C6M") (class "Default")
      (node (ref "CCM6") (pin "1") (pinfunction "1_1") (pintype "passive"))
      (node (ref "CCM7") (pin "2") (pinfunction "2_2") (pintype "passive"))
      (node (ref "DCM6") (pin "C") (pinfunction "C_C") (pintype "passive"))
      (node (ref "DCM7") (pin "A") (pinfunction "A_A") (pintype "passive"))
      (node (ref "IC2") (pin "14") (pinfunction "C6_14") (pintype "bidirectional"))
      (node (ref "RCM6") (pin "2") (pinfunction "2_2") (pintype "passive"))
    )
    (net (code "27") (name "C7") (class "Default")
      (node (ref "QB7") (pin "2") (pinfunction "S_2") (pintype "passive"))
      (node (ref "RCM7") (pin "1") (pinfunction "1_1") (pintype "passive"))
      (node (ref "RP8") (pin "1") (pinfunction "1_1") (pintype "passive"))
      (node (ref "X6") (pin "4") (pinfunction "4_4") (pintype "passive"))
    )
    (net (code "28") (name "C7M") (class "Default")
      (node (ref "CCM7") (pin "1") (pinfunction "1_1") (pintype "passive"))
      (node (ref "CCM8") (pin "2") (pinfunction "2_2") (pintype "passive"))
      (node (ref "DCM7") (pin "C") (pinfunction "C_C") (pintype "passive"))
      (node (ref "DCM8") (pin "A") (pinfunction "A_A") (pintype "passive"))
      (node (ref "IC2") (pin "12") (pinfunction "C7_12") (pintype "bidirectional"))
      (node (ref "RCM7") (pin "2") (pinfunction "2_2") (pintype "passive"))
    )
    (net (code "29") (name "C8") (class "Default")
      (node (ref "QB8") (pin "2") (pinfunction "S_2") (pintype "passive"))
      (node (ref "RCM8") (pin "1") (pinfunction "1_1") (pintype "passive"))
      (node (ref "RP9") (pin "1") (pinfunction "1_1") (pintype "passive"))
      (node (ref "X3") (pin "3") (pinfunction "3_3") (pintype "passive"))
    )
    (net (code "30") (name "C8M") (class "Default")
      (node (ref "CCM8") (pin "1") (pinfunction "1_1") (pintype "passive"))
      (node (ref "CCM9") (pin "2") (pinfunction "2_2") (pintype "passive"))
      (node (ref "DCM8") (pin "C") (pinfunction "C_C") (pintype "passive"))
      (node (ref "DCM9") (pin "A") (pinfunction "A_A") (pintype "passive"))
      (node (ref "IC2") (pin "10") (pinfunction "C8_10") (pintype "bidirectional"))
      (node (ref "RCM8") (pin "2") (pinfunction "2_2") (pintype "passive"))
    )
    (net (code "31") (name "C9") (class "Default")
      (node (ref "QB9") (pin "2") (pinfunction "S_2") (pintype "passive"))
      (node (ref "RCM9") (pin "1") (pinfunction "1_1") (pintype "passive"))
      (node (ref "RP10") (pin "1") (pinfunction "1_1") (pintype "passive"))
      (node (ref "X6") (pin "5") (pinfunction "5_5") (pintype "passive"))
    )
    (net (code "32") (name "C9M") (class "Default")
      (node (ref "CCM10") (pin "2") (pinfunction "2_2") (pintype "passive"))
      (node (ref "CCM9") (pin "1") (pinfunction "1_1") (pintype "passive"))
      (node (ref "DCM10") (pin "A") (pinfunction "A_A") (pintype "passive"))
      (node (ref "DCM9") (pin "C") (pinfunction "C_C") (pintype "passive"))
      (node (ref "IC2") (pin "8") (pinfunction "C9_8") (pintype "bidirectional"))
      (node (ref "RCM9") (pin "2") (pinfunction "2_2") (pintype "passive"))
    )
    (net (code "33") (name "C10") (class "Default")
      (node (ref "QB10") (pin "2") (pinfunction "S_2") (pintype "passive"))
      (node (ref "RCM10") (pin "1") (pinfunction "1_1") (pintype "passive"))
      (node (ref "RP11") (pin "1") (pinfunction "1_1") (pintype "passive"))
      (node (ref "X3") (pin "2") (pinfunction "1_2") (pintype "passive"))
    )
    (net (code "34") (name "C10M") (class "Default")
      (node (ref "CCM10") (pin "1") (pinfunction "1_1") (pintype "passive"))
      (node (ref "CCM11") (pin "2") (pinfunction "2_2") (pintype "passive"))
      (node (ref "DCM10") (pin "C") (pinfunction "C_C") (pintype "passive"))
      (node (ref "DCM11") (pin "A") (pinfunction "A_A") (pintype "passive"))
      (node (ref "IC2") (pin "6") (pinfunction "C10_6") (pintype "bidirectional"))
      (node (ref "RCM10") (pin "2") (pinfunction "2_2") (pintype "passive"))
    )
    (net (code "35") (name "C11") (class "Default")
      (node (ref "QB11") (pin "2") (pinfunction "S_2") (pintype "passive"))
      (node (ref "RCM11") (pin "1") (pinfunction "1_1") (pintype "passive"))
      (node (ref "RP12") (pin "1") (pinfunction "1_1") (pintype "passive"))
      (node (ref "X6") (pin "6") (pinfunction "6_6") (pintype "passive"))
    )
    (net (code "36") (name "C11M") (class "Default")
      (node (ref "CCM11") (pin "1") (pinfunction "1_1") (pintype "passive"))
      (node (ref "CCM12") (pin "2") (pinfunction "2_2") (pintype "passive"))
      (node (ref "DCM11") (pin "C") (pinfunction "C_C") (pintype "passive"))
      (node (ref "DCM12") (pin "A") (pinfunction "A_A") (pintype "passive"))
      (node (ref "IC2") (pin "4") (pinfunction "C11_4") (pintype "bidirectional"))
      (node (ref "RCM11") (pin "2") (pinfunction "2_2") (pintype "passive"))
    )
    (net (code "37") (name "C12") (class "Default")
      (node (ref "L7") (pin "1") (pinfunction "1_1") (pintype "passive"))
      (node (ref "QB12") (pin "2") (pinfunction "S_2") (pintype "passive"))
      (node (ref "RCM12") (pin "1") (pinfunction "1_1") (pintype "passive"))
      (node (ref "X3") (pin "1") (pinfunction "2_1") (pintype "passive"))
    )
    (net (code "38") (name "C12M") (class "Default")
      (node (ref "CCM12") (pin "1") (pinfunction "1_1") (pintype "passive"))
      (node (ref "DCM12") (pin "C") (pinfunction "C_C") (pintype "passive"))
      (node (ref "IC2") (pin "2") (pinfunction "C12_2") (pintype "bidirectional"))
      (node (ref "RCM12") (pin "2") (pinfunction "2_2") (pintype "passive"))
    )
    (net (code "39") (name "CANH") (class "Default")
      (node (ref "L12") (pin "4") (pinfunction "4_4") (pintype "passive"))
      (node (ref "RV3") (pin "1") (pinfunction "1_1") (pintype "passive"))
      (node (ref "X7") (pin "3") (pinfunction "3_3") (pintype "passive"))
      (node (ref "X7") (pin "7") (pinfunction "7_7") (pintype "passive"))
    )
    (net (code "40") (name "CANL") (class "Default")
      (node (ref "L12") (pin "3") (pinfunction "2_3") (pintype "passive"))
      (node (ref "RV2") (pin "1") (pinfunction "1_1") (pintype "passive"))
      (node (ref "X7") (pin "2") (pinfunction "2_2") (pintype "passive"))
      (node (ref "X7") (pin "6") (pinfunction "6_6") (pintype "passive"))
    )
    (net (code "41") (name "CANRX") (class "Default")
      (node (ref "R7") (pin "2") (pinfunction "2_2") (pintype "passive"))
      (node (ref "U$2") (pin "P$14") (pinfunction "O1_P$14") (pintype "bidirectional"))
    )
    (net (code "42") (name "CANTX") (class "Default")
      (node (ref "R6") (pin "2") (pinfunction "2_2") (pintype "passive"))
      (node (ref "U$2") (pin "P$13") (pinfunction "I2_P$13") (pintype "bidirectional"))
    )
    (net (code "43") (name "CAR+5V") (class "Default")
      (node (ref "C17") (pin "1") (pinfunction "1_1") (pintype "passive"))
      (node (ref "C6") (pin "1") (pinfunction "1_1") (pintype "passive"))
      (node (ref "C7") (pin "1") (pinfunction "1_1") (pintype "passive"))
      (node (ref "IC5") (pin "3") (pinfunction "VDD_3") (pintype "bidirectional"))
      (node (ref "JP1") (pin "1") (pinfunction "1_1") (pintype "passive"))
      (node (ref "REG5_C3") (pin "1") (pinfunction "1_1") (pintype "passive"))
      (node (ref "REG5_C5") (pin "1") (pinfunction "1_1") (pintype "passive"))
      (node (ref "REG5_D1") (pin "A") (pinfunction "A_A") (pintype "passive"))
      (node (ref "REG5_L") (pin "2") (pinfunction "2_2") (pintype "passive"))
      (node (ref "REG5_R2") (pin "2") (pinfunction "2_2") (pintype "passive"))
      (node (ref "U$2") (pin "P$1") (pinfunction "VDD_P$1") (pintype "bidirectional"))
      (node (ref "U$2") (pin "P$6") (pinfunction "RCSEL_P$6") (pintype "bidirectional"))
      (node (ref "U$2") (pin "P$7") (pinfunction "EN1_P$7") (pintype "bidirectional"))
    )
    (net (code "44") (name "CARGND") (class "Default")
      (node (ref "C17") (pin "2") (pinfunction "2_2") (pintype "passive"))
      (node (ref "C6") (pin "2") (pinfunction "2_2") (pintype "passive"))
      (node (ref "C7") (pin "2") (pinfunction "2_2") (pintype "passive"))
      (node (ref "IC3") (pin "2") (pinfunction "GND_2") (pintype "bidirectional"))
      (node (ref "IC5") (pin "2") (pinfunction "VSS_2") (pintype "bidirectional"))
      (node (ref "R39") (pin "2") (pinfunction "2_2") (pintype "passive"))
      (node (ref "REG5_C1") (pin "2") (pinfunction "2_2") (pintype "passive"))
      (node (ref "REG5_C3") (pin "2") (pinfunction "2_2") (pintype "passive"))
      (node (ref "REG5_C4") (pin "2") (pinfunction "2_2") (pintype "passive"))
      (node (ref "REG5_C5") (pin "2") (pinfunction "2_2") (pintype "passive"))
      (node (ref "REG5_D2") (pin "2") (pinfunction "A_2") (pintype "passive"))
      (node (ref "REG5_R1") (pin "1") (pinfunction "1_1") (pintype "passive"))
      (node (ref "RV1") (pin "2") (pinfunction "2_2") (pintype "passive"))
      (node (ref "RV2") (pin "2") (pinfunction "2_2") (pintype "passive"))
      (node (ref "RV3") (pin "2") (pinfunction "2_2") (pintype "passive"))
      (node (ref "U$2") (pin "P$2") (pinfunction "GND_P$2") (pintype "bidirectional"))
      (node (ref "U$2") (pin "P$5") (pinfunction "RCIN_P$5") (pintype "bidirectional"))
      (node (ref "U$2") (pin "P$8") (pinfunction "GND_P$8") (pintype "bidirectional"))
      (node (ref "X7") (pin "4") (pinfunction "4_4") (pintype "passive"))
      (node (ref "X7") (pin "8") (pinfunction "8_8") (pintype "passive"))
    )
    (net (code "45") (name "CARVIN") (class "Default")
      (node (ref "L2") (pin "1") (pinfunction "1_1") (pintype "passive"))
      (node (ref "REG5_C4") (pin "1") (pinfunction "1_1") (pintype "passive"))
      (node (ref "RV1") (pin "1") (pinfunction "1_1") (pintype "passive"))
      (node (ref "X7") (pin "1") (pinfunction "1_1") (pintype "passive"))
      (node (ref "X7") (pin "5") (pinfunction "5_5") (pintype "passive"))
    )
    (net (code "46") (name "CSB") (class "Default")
      (node (ref "IC2") (pin "44") (pinfunction "CSBI_44") (pintype "bidirectional"))
      (node (ref "R1") (pin "2") (pinfunction "2_2") (pintype "passive"))
    )
    (net (code "47") (name "FSM") (class "Default")
      (node (ref "C2") (pin "1") (pinfunction "1_1") (pintype "passive"))
      (node (ref "C4") (pin "1") (pinfunction "1_1") (pintype "passive"))
      (node (ref "IC1") (pin "30") (pinfunction "PIO1_10/AD6/CT16B1_MAT1_30") (pintype "bidirectional"))
      (node (ref "IC2") (pin "29") (pinfunction "VTEMP1_29") (pintype "bidirectional"))
      (node (ref "R59") (pin "1") (pinfunction "1_1") (pintype "passive"))
      (node (ref "R60") (pin "2") (pinfunction "2_2") (pintype "passive"))
    )
    (net (code "48") (name "GND") (class "Default")
      (node (ref "C1") (pin "2") (pinfunction "2_2") (pintype "passive"))
      (node (ref "C14") (pin "1") (pinfunction "1_1") (pintype "passive"))
      (node (ref "C15") (pin "1") (pinfunction "1_1") (pintype "passive"))
      (node (ref "C2") (pin "2") (pinfunction "2_2") (pintype "passive"))
      (node (ref "C22") (pin "2") (pinfunction "2_2") (pintype "passive"))
      (node (ref "C23") (pin "2") (pinfunction "2_2") (pintype "passive"))
      (node (ref "C27") (pin "2") (pinfunction "2_2") (pintype "passive"))
      (node (ref "C3") (pin "2") (pinfunction "2_2") (pintype "passive"))
      (node (ref "C34") (pin "2") (pinfunction "2_2") (pintype "passive"))
      (node (ref "C4") (pin "2") (pinfunction "2_2") (pintype "passive"))
      (node (ref "C5") (pin "2") (pinfunction "2_2") (pintype "passive"))
      (node (ref "CVREF") (pin "1") (pinfunction "1_1") (pintype "passive"))
      (node (ref "CVREG") (pin "1") (pinfunction "1_1") (pintype "passive"))
      (node (ref "DT1") (pin "C") (pinfunction "C_C") (pintype "passive"))
      (node (ref "DT2") (pin "C") (pinfunction "C_C") (pintype "passive"))
      (node (ref "DT3") (pin "C") (pinfunction "C_C") (pintype "passive"))
      (node (ref "DT4") (pin "C") (pinfunction "C_C") (pintype "passive"))
      (node (ref "DT5") (pin "C") (pinfunction "C_C") (pintype "passive"))
      (node (ref "DT6") (pin "C") (pinfunction "C_C") (pintype "passive"))
      (node (ref "IC1") (pin "41") (pinfunction "VSS_41") (pintype "bidirectional"))
      (node (ref "IC1") (pin "5") (pinfunction "VSS_5") (pintype "bidirectional"))
      (node (ref "IC2") (pin "27") (pinfunction "V-_27") (pintype "bidirectional"))
      (node (ref "IC2") (pin "33") (pinfunction "TOS_33") (pintype "bidirectional"))
      (node (ref "IC2") (pin "34") (pinfunction "WDTB_34") (pintype "bidirectional"))
      (node (ref "IC2") (pin "35") (pinfunction "GPIO1_35") (pintype "bidirectional"))
      (node (ref "IC2") (pin "36") (pinfunction "GPIO2_36") (pintype "bidirectional"))
      (node (ref "IC2") (pin "37") (pinfunction "A0_37") (pintype "bidirectional"))
      (node (ref "IC2") (pin "38") (pinfunction "A1_38") (pintype "bidirectional"))
      (node (ref "IC2") (pin "39") (pinfunction "A2_39") (pintype "bidirectional"))
      (node (ref "IC2") (pin "40") (pinfunction "A3_40") (pintype "bidirectional"))
      (node (ref "J1") (pin "6") (pinfunction "6_6") (pintype "passive"))
      (node (ref "NTC_C1") (pin "2") (pinfunction "2_2") (pintype "passive"))
      (node (ref "NTC_C2") (pin "2") (pinfunction "2_2") (pintype "passive"))
      (node (ref "NTC_C3") (pin "2") (pinfunction "2_2") (pintype "passive"))
      (node (ref "NTC_C4") (pin "2") (pinfunction "2_2") (pintype "passive"))
      (node (ref "Q2") (pin "2") (pinfunction "S_2") (pintype "passive"))
      (node (ref "R11") (pin "1") (pinfunction "1_1") (pintype "passive"))
      (node (ref "R60") (pin "1") (pinfunction "1_1") (pintype "passive"))
      (node (ref "RGQ1_3") (pin "1") (pinfunction "1_1") (pintype "passive"))
      (node (ref "U$2") (pin "P$11") (pinfunction "VSEL_P$11") (pintype "bidirectional"))
      (node (ref "U$2") (pin "P$15") (pinfunction "GNDISO_P$15") (pintype "bidirectional"))
      (node (ref "U$2") (pin "P$9") (pinfunction "GNDISO_P$9") (pintype "bidirectional"))
      (node (ref "V-R") (pin "2") (pinfunction "2_2") (pintype "passive"))
      (node (ref "X1") (pin "3") (pinfunction "3_3") (pintype "passive"))
      (node (ref "Y1") (pin "P2") (pinfunction "GND_P2") (pintype "bidirectional"))
      (node (ref "Y1") (pin "P4") (pinfunction "GND1_P4") (pintype "bidirectional"))
    )
    (net (code "49") (name "ISP_CAN") (class "Default")
      (node (ref "IC1") (pin "14") (pinfunction "PIO0_3_14") (pintype "bidirectional"))
      (node (ref "R11") (pin "2") (pinfunction "2_2") (pintype "passive"))
    )
    (net (code "50") (name "ISP_ENTER") (class "Default")
      (node (ref "IC1") (pin "4") (pinfunction "PIO0_1/CLKOUT/CT32B0_MAT2_4") (pintype "bidirectional"))
      (node (ref "J1") (pin "5") (pinfunction "5_5") (pintype "passive"))
      (node (ref "R15") (pin "2") (pinfunction "2_2") (pintype "passive"))
    )
    (net (code "51") (name "LED1") (class "Default")
      (node (ref "IC1") (pin "24") (pinfunction "PIO2_9_24") (pintype "bidirectional"))
      (node (ref "LED1") (pin "C") (pinfunction "C_C") (pintype "passive"))
    )
    (net (code "52") (name "LED2") (class "Default")
      (node (ref "IC1") (pin "25") (pinfunction "PIO2_10_25") (pintype "bidirectional"))
      (node (ref "LED2") (pin "C") (pinfunction "C_C") (pintype "passive"))
    )
    (net (code "53") (name "MISO0") (class "Default")
      (node (ref "IC1") (pin "27") (pinfunction "PIO0_8/MISO0/CT16B0_MAT0_27") (pintype "bidirectional"))
      (node (ref "R4") (pin "1") (pinfunction "1_1") (pintype "passive"))
    )
    (net (code "54") (name "MISO1") (class "Default")
      (node (ref "IC1") (pin "26") (pinfunction "PIO2_2/~{DCD}/MISO1_26") (pintype "bidirectional"))
    )
    (net (code "55") (name "MOSI0") (class "Default")
      (node (ref "IC1") (pin "28") (pinfunction "PIO0_9/MOSI0/CT16B0_MAT1_28") (pintype "bidirectional"))
      (node (ref "R5") (pin "1") (pinfunction "1_1") (pintype "passive"))
    )
    (net (code "56") (name "MOSI1") (class "Default")
      (node (ref "IC1") (pin "38") (pinfunction "PIO2_3/~{RI}/MOSI1_38") (pintype "bidirectional"))
    )
    (net (code "57") (name "Net-(IC1-CANRX)") (class "Default")
      (node (ref "IC1") (pin "19") (pinfunction "CANRX_19") (pintype "bidirectional"))
      (node (ref "R7") (pin "1") (pinfunction "1_1") (pintype "passive"))
    )
    (net (code "58") (name "Net-(IC1-CANTX)") (class "Default")
      (node (ref "IC1") (pin "20") (pinfunction "CANTX_20") (pintype "bidirectional"))
      (node (ref "R6") (pin "1") (pinfunction "1_1") (pintype "passive"))
    )
    (net (code "59") (name "Net-(IC1-XTALIN)") (class "Default")
      (node (ref "C15") (pin "2") (pinfunction "2_2") (pintype "passive"))
      (node (ref "IC1") (pin "6") (pinfunction "XTALIN_6") (pintype "bidirectional"))
      (node (ref "Y1") (pin "P3") (pinfunction "2_P3") (pintype "passive"))
    )
    (net (code "60") (name "Net-(IC1-XTALOUT)") (class "Default")
      (node (ref "C14") (pin "2") (pinfunction "2_2") (pintype "passive"))
      (node (ref "IC1") (pin "7") (pinfunction "XTALOUT_7") (pintype "bidirectional"))
      (node (ref "Y1") (pin "P1") (pinfunction "1_P1") (pintype "passive"))
    )
    (net (code "61") (name "Net-(IC3-BOOST)") (class "Default")
      (node (ref "IC3") (pin "1") (pinfunction "BOOST_1") (pintype "bidirectional"))
      (node (ref "REG5_C2") (pin "1") (pinfunction "1_1") (pintype "passive"))
      (node (ref "REG5_D1") (pin "C") (pinfunction "C_C") (pintype "passive"))
    )
    (net (code "62") (name "Net-(IC3-FB)") (class "Default")
      (node (ref "IC3") (pin "3") (pinfunction "FB_3") (pintype "bidirectional"))
      (node (ref "REG5_R1") (pin "2") (pinfunction "2_2") (pintype "passive"))
      (node (ref "REG5_R2") (pin "1") (pinfunction "1_1") (pintype "passive"))
    )
    (net (code "63") (name "Net-(IC3-SW)") (class "Default")
      (node (ref "IC3") (pin "6") (pinfunction "SW_6") (pintype "bidirectional"))
      (node (ref "REG5_C2") (pin "2") (pinfunction "2_2") (pintype "passive"))
      (node (ref "REG5_D2") (pin "1") (pinfunction "C_1") (pintype "passive"))
      (node (ref "REG5_L") (pin "1") (pinfunction "1_1") (pintype "passive"))
    )
    (net (code "64") (name "Net-(IC3-VIN)") (class "Default")
      (node (ref "IC3") (pin "4") (pinfunction "~{SHDN}_4") (pintype "bidirectional"))
      (node (ref "IC3") (pin "5") (pinfunction "VIN_5") (pintype "bidirectional"))
      (node (ref "L2") (pin "2") (pinfunction "2_2") (pintype "passive"))
      (node (ref "REG5_C1") (pin "1") (pinfunction "1_1") (pintype "passive"))
    )
    (net (code "65") (name "Net-(IC5-CANH)") (class "Default")
      (node (ref "IC5") (pin "7") (pinfunction "CANH_7") (pintype "bidirectional"))
      (node (ref "L12") (pin "1") (pinfunction "3_1") (pintype "passive"))
    )
    (net (code "66") (name "Net-(IC5-CANL)") (class "Default")
      (node (ref "IC5") (pin "6") (pinfunction "CANL_6") (pintype "bidirectional"))
      (node (ref "L12") (pin "2") (pinfunction "1_2") (pintype "passive"))
    )
    (net (code "67") (name "Net-(IC5-RS)") (class "Default")
      (node (ref "IC5") (pin "8") (pinfunction "RS_8") (pintype "bidirectional"))
      (node (ref "R39") (pin "1") (pinfunction "1_1") (pintype "passive"))
    )
    (net (code "68") (name "Net-(IC5-RX)") (class "Default")
      (node (ref "IC5") (pin "4") (pinfunction "RX_4") (pintype "bidirectional"))
      (node (ref "R41") (pin "1") (pinfunction "1_1") (pintype "passive"))
    )
    (net (code "69") (name "Net-(IC5-TX)") (class "Default")
      (node (ref "IC5") (pin "1") (pinfunction "TX_1") (pintype "bidirectional"))
      (node (ref "R40") (pin "1") (pinfunction "1_1") (pintype "passive"))
    )
    (net (code "70") (name "Net-(L7-Pad2)") (class "Default")
      (node (ref "L7") (pin "2") (pinfunction "2_2") (pintype "passive"))
      (node (ref "V+R") (pin "1") (pinfunction "1_1") (pintype "passive"))
    )
    (net (code "71") (name "Net-(LED1-PadA)") (class "Default")
      (node (ref "LED1") (pin "A") (pinfunction "A_A") (pintype "passive"))
      (node (ref "R2") (pin "1") (pinfunction "1_1") (pintype "passive"))
    )
    (net (code "72") (name "Net-(LED2-PadA)") (class "Default")
      (node (ref "LED2") (pin "A") (pinfunction "A_A") (pintype "passive"))
      (node (ref "R8") (pin "1") (pinfunction "1_1") (pintype "passive"))
    )
    (net (code "73") (name "Net-(Q1-G)") (class "Default")
      (node (ref "D2") (pin "A") (pinfunction "A_A") (pintype "passive"))
      (node (ref "Q1") (pin "1") (pinfunction "G_1") (pintype "passive"))
      (node (ref "RGQ1_1") (pin "2") (pinfunction "2_2") (pintype "passive"))
      (node (ref "RGQ1_2") (pin "2") (pinfunction "2_2") (pintype "passive"))
    )
    (net (code "74") (name "Net-(Q1-S)") (class "Default")
      (node (ref "D1") (pin "C") (pinfunction "C_C") (pintype "passive"))
      (node (ref "D2") (pin "C") (pinfunction "C_C") (pintype "passive"))
      (node (ref "Q1") (pin "2") (pinfunction "S_2") (pintype "passive"))
      (node (ref "RGQ1_1") (pin "1") (pinfunction "1_1") (pintype "passive"))
      (node (ref "V+R") (pin "2") (pinfunction "2_2") (pintype "passive"))
    )
    (net (code "75") (name "Net-(Q2-D)") (class "Default")
      (node (ref "Q2") (pin "3") (pinfunction "D_3") (pintype "passive"))
      (node (ref "RGQ1_2") (pin "1") (pinfunction "1_1") (pintype "passive"))
    )
    (net (code "76") (name "Net-(QB1-D)") (class "Default")
      (node (ref "QB1") (pin "3") (pinfunction "D_3") (pintype "passive"))
      (node (ref "RP1") (pin "2") (pinfunction "2_2") (pintype "passive"))
    )
    (net (code "77") (name "Net-(QB1-G)") (class "Default")
      (node (ref "QB1") (pin "1") (pinfunction "G_1") (pintype "passive"))
      (node (ref "RBG1") (pin "1") (pinfunction "1_1") (pintype "passive"))
    )
    (net (code "78") (name "Net-(QB2-D)") (class "Default")
      (node (ref "QB2") (pin "3") (pinfunction "D_3") (pintype "passive"))
      (node (ref "RP2") (pin "2") (pinfunction "2_2") (pintype "passive"))
    )
    (net (code "79") (name "Net-(QB2-G)") (class "Default")
      (node (ref "QB2") (pin "1") (pinfunction "G_1") (pintype "passive"))
      (node (ref "RBG2") (pin "1") (pinfunction "1_1") (pintype "passive"))
    )
    (net (code "80") (name "Net-(QB3-D)") (class "Default")
      (node (ref "QB3") (pin "3") (pinfunction "D_3") (pintype "passive"))
      (node (ref "RP3") (pin "2") (pinfunction "2_2") (pintype "passive"))
    )
    (net (code "81") (name "Net-(QB3-G)") (class "Default")
      (node (ref "QB3") (pin "1") (pinfunction "G_1") (pintype "passive"))
      (node (ref "RBG3") (pin "1") (pinfunction "1_1") (pintype "passive"))
    )
    (net (code "82") (name "Net-(QB4-D)") (class "Default")
      (node (ref "QB4") (pin "3") (pinfunction "D_3") (pintype "passive"))
      (node (ref "RP4") (pin "2") (pinfunction "2_2") (pintype "passive"))
    )
    (net (code "83") (name "Net-(QB4-G)") (class "Default")
      (node (ref "QB4") (pin "1") (pinfunction "G_1") (pintype "passive"))
      (node (ref "RBG4") (pin "1") (pinfunction "1_1") (pintype "passive"))
    )
    (net (code "84") (name "Net-(QB5-D)") (class "Default")
      (node (ref "QB5") (pin "3") (pinfunction "D_3") (pintype "passive"))
      (node (ref "RP5") (pin "2") (pinfunction "2_2") (pintype "passive"))
    )
    (net (code "85") (name "Net-(QB5-G)") (class "Default")
      (node (ref "QB5") (pin "1") (pinfunction "G_1") (pintype "passive"))
      (node (ref "RBG5") (pin "1") (pinfunction "1_1") (pintype "passive"))
    )
    (net (code "86") (name "Net-(QB6-D)") (class "Default")
      (node (ref "QB6") (pin "3") (pinfunction "D_3") (pintype "passive"))
      (node (ref "RP6") (pin "2") (pinfunction "2_2") (pintype "passive"))
    )
    (net (code "87") (name "Net-(QB6-G)") (class "Default")
      (node (ref "QB6") (pin "1") (pinfunction "G_1") (pintype "passive"))
      (node (ref "RBG6") (pin "1") (pinfunction "1_1") (pintype "passive"))
    )
    (net (code "88") (name "Net-(QB7-D)") (class "Default")
      (node (ref "QB7") (pin "3") (pinfunction "D_3") (pintype "passive"))
      (node (ref "RP7") (pin "2") (pinfunction "2_2") (pintype "passive"))
    )
    (net (code "89") (name "Net-(QB7-G)") (class "Default")
      (node (ref "QB7") (pin "1") (pinfunction "G_1") (pintype "passive"))
      (node (ref "RBG7") (pin "1") (pinfunction "1_1") (pintype "passive"))
    )
    (net (code "90") (name "Net-(QB8-D)") (class "Default")
      (node (ref "QB8") (pin "3") (pinfunction "D_3") (pintype "passive"))
      (node (ref "RP8") (pin "2") (pinfunction "2_2") (pintype "passive"))
    )
    (net (code "91") (name "Net-(QB8-G)") (class "Default")
      (node (ref "QB8") (pin "1") (pinfunction "G_1") (pintype "passive"))
      (node (ref "RBG8") (pin "1") (pinfunction "1_1") (pintype "passive"))
    )
    (net (code "92") (name "Net-(QB9-D)") (class "Default")
      (node (ref "QB9") (pin "3") (pinfunction "D_3") (pintype "passive"))
      (node (ref "RP9") (pin "2") (pinfunction "2_2") (pintype "passive"))
    )
    (net (code "93") (name "Net-(QB9-G)") (class "Default")
      (node (ref "QB9") (pin "1") (pinfunction "G_1") (pintype "passive"))
      (node (ref "RBG9") (pin "1") (pinfunction "1_1") (pintype "passive"))
    )
    (net (code "94") (name "Net-(QB10-D)") (class "Default")
      (node (ref "QB10") (pin "3") (pinfunction "D_3") (pintype "passive"))
      (node (ref "RP10") (pin "2") (pinfunction "2_2") (pintype "passive"))
    )
    (net (code "95") (name "Net-(QB10-G)") (class "Default")
      (node (ref "QB10") (pin "1") (pinfunction "G_1") (pintype "passive"))
      (node (ref "RBG10") (pin "1") (pinfunction "1_1") (pintype "passive"))
    )
    (net (code "96") (name "Net-(QB11-D)") (class "Default")
      (node (ref "QB11") (pin "3") (pinfunction "D_3") (pintype "passive"))
      (node (ref "RP11") (pin "2") (pinfunction "2_2") (pintype "passive"))
    )
    (net (code "97") (name "Net-(QB11-G)") (class "Default")
      (node (ref "QB11") (pin "1") (pinfunction "G_1") (pintype "passive"))
      (node (ref "RBG11") (pin "1") (pinfunction "1_1") (pintype "passive"))
    )
    (net (code "98") (name "Net-(QB12-D)") (class "Default")
      (node (ref "QB12") (pin "3") (pinfunction "D_3") (pintype "passive"))
      (node (ref "RP12") (pin "2") (pinfunction "2_2") (pintype "passive"))
    )
    (net (code "99") (name "Net-(QB12-G)") (class "Default")
      (node (ref "QB12") (pin "1") (pinfunction "G_1") (pintype "passive"))
      (node (ref "RBG12") (pin "1") (pinfunction "1_1") (pintype "passive"))
    )
    (net (code "100") (name "Net-(U$2-I1)") (class "Default")
      (node (ref "R41") (pin "2") (pinfunction "2_2") (pintype "passive"))
      (node (ref "U$2") (pin "P$3") (pinfunction "I1_P$3") (pintype "bidirectional"))
    )
    (net (code "101") (name "Net-(U$2-O2)") (class "Default")
      (node (ref "R40") (pin "2") (pinfunction "2_2") (pintype "passive"))
      (node (ref "U$2") (pin "P$4") (pinfunction "O2_P$4") (pintype "bidirectional"))
    )
    (net (code "102") (name "SCK") (class "Default")
      (node (ref "IC2") (pin "41") (pinfunction "SCKI_41") (pintype "bidirectional"))
      (node (ref "R3") (pin "2") (pinfunction "2_2") (pintype "passive"))
    )
    (net (code "103") (name "SCK0") (class "Default")
      (node (ref "IC1") (pin "22") (pinfunction "PIO0_6/SCK0_22") (pintype "bidirectional"))
      (node (ref "R3") (pin "1") (pinfunction "1_1") (pintype "passive"))
    )
    (net (code "104") (name "SCK1") (class "Default")
      (node (ref "IC1") (pin "13") (pinfunction "PIO2_1/~{DSR}/SCK1_13") (pintype "bidirectional"))
    )
    (net (code "105") (name "SDI") (class "Default")
      (node (ref "IC2") (pin "42") (pinfunction "SDI_42") (pintype "bidirectional"))
      (node (ref "R5") (pin "2") (pinfunction "2_2") (pintype "passive"))
    )
    (net (code "106") (name "SDO") (class "Default")
      (node (ref "IC2") (pin "43") (pinfunction "SDO_43") (pintype "bidirectional"))
      (node (ref "R19") (pin "1") (pinfunction "1_1") (pintype "passive"))
      (node (ref "R4") (pin "2") (pinfunction "2_2") (pintype "passive"))
    )
    (net (code "107") (name "SSEL0") (class "Default")
      (node (ref "IC1") (pin "10") (pinfunction "PIO0_2/SSEL/CT16B0_CAP0_10") (pintype "bidirectional"))
      (node (ref "R1") (pin "1") (pinfunction "1_1") (pintype "passive"))
    )
    (net (code "108") (name "SSEL1") (class "Default")
      (node (ref "IC1") (pin "2") (pinfunction "PIO2_0/~{DTR}/SSEL1_2") (pintype "bidirectional"))
    )
    (net (code "109") (name "SWCLK") (class "Default")
      (node (ref "IC1") (pin "29") (pinfunction "PIO0_10/SWCLK/SCK0/CT16B0_MAT2_29") (pintype "bidirectional"))
      (node (ref "J1") (pin "4") (pinfunction "4_4") (pintype "passive"))
    )
    (net (code "110") (name "SWDIO") (class "Default")
      (node (ref "IC1") (pin "39") (pinfunction "PIO1_3/SWDIO/AD4/CT32B1_MAT2_39") (pintype "bidirectional"))
      (node (ref "J1") (pin "3") (pinfunction "3_3") (pintype "passive"))
    )
    (net (code "111") (name "TEMP0") (class "Default")
      (node (ref "IC1") (pin "42") (pinfunction "PIO1_11/AD7_42") (pintype "bidirectional"))
      (node (ref "NTC_C3") (pin "1") (pinfunction "1_1") (pintype "passive"))
      (node (ref "NTC_R3") (pin "1") (pinfunction "1_1") (pintype "passive"))
      (node (ref "X1") (pin "1") (pinfunction "2_1") (pintype "passive"))
    )
    (net (code "112") (name "TEMP1") (class "Default")
      (node (ref "IC1") (pin "40") (pinfunction "PIO1_4/AD5/CT32B1_MAT3_40") (pintype "bidirectional"))
      (node (ref "NTC_C2") (pin "1") (pinfunction "1_1") (pintype "passive"))
      (node (ref "NTC_R2") (pin "1") (pinfunction "1_1") (pintype "passive"))
      (node (ref "X1") (pin "2") (pinfunction "1_2") (pintype "passive"))
    )
    (net (code "113") (name "TEMP2") (class "Default")
      (node (ref "IC1") (pin "35") (pinfunction "PIO1_2/AD3/CT32B1_MAT1_35") (pintype "bidirectional"))
      (node (ref "NTC_C4") (pin "1") (pinfunction "1_1") (pintype "passive"))
      (node (ref "NTC_R4") (pin "1") (pinfunction "1_1") (pintype "passive"))
      (node (ref "X1") (pin "4") (pinfunction "4_4") (pintype "passive"))
    )
    (net (code "114") (name "TEMP3") (class "Default")
      (node (ref "IC1") (pin "34") (pinfunction "PIO1_1/AD2/CT32B1_MAT0_34") (pintype "bidirectional"))
      (node (ref "NTC_C1") (pin "1") (pinfunction "1_1") (pintype "passive"))
      (node (ref "NTC_R1") (pin "1") (pinfunction "1_1") (pintype "passive"))
      (node (ref "X1") (pin "5") (pinfunction "5_5") (pintype "passive"))
    )
    (net (code "115") (name "TEMPR") (class "Default")
      (node (ref "C3") (pin "1") (pinfunction "1_1") (pintype "passive"))
      (node (ref "DT1") (pin "A") (pinfunction "A_A") (pintype "passive"))
      (node (ref "DT2") (pin "A") (pinfunction "A_A") (pintype "passive"))
      (node (ref "DT3") (pin "A") (pinfunction "A_A") (pintype "passive"))
      (node (ref "DT4") (pin "A") (pinfunction "A_A") (pintype "passive"))
      (node (ref "DT5") (pin "A") (pinfunction "A_A") (pintype "passive"))
      (node (ref "DT6") (pin "A") (pinfunction "A_A") (pintype "passive"))
      (node (ref "IC1") (pin "33") (pinfunction "PIO1_0/AD1/CT32B1_CAP0_33") (pintype "bidirectional"))
      (node (ref "R9") (pin "1") (pinfunction "1_1") (pintype "passive"))
    )
    (net (code "116") (name "V+") (class "Default")
      (node (ref "C1") (pin "1") (pinfunction "1_1") (pintype "passive"))
      (node (ref "IC2") (pin "1") (pinfunction "V+_1") (pintype "bidirectional"))
      (node (ref "Q1") (pin "3") (pinfunction "D_3") (pintype "passive"))
      (node (ref "R59") (pin "2") (pinfunction "2_2") (pintype "passive"))
    )
    (net (code "117") (name "VREF") (class "Default")
      (node (ref "CVREF") (pin "2") (pinfunction "2_2") (pintype "passive"))
      (node (ref "IC2") (pin "31") (pinfunction "VREF_31") (pintype "bidirectional"))
    )
    (net (code "118") (name "VREG") (class "Default")
      (node (ref "CVREG") (pin "2") (pinfunction "2_2") (pintype "passive"))
      (node (ref "IC2") (pin "32") (pinfunction "VREG_32") (pintype "bidirectional"))
    )
    (net (code "119") (name "unconnected-(IC1-PIO0_4{slash}SCL-Pad15)") (class "Default")
      (node (ref "IC1") (pin "15") (pinfunction "PIO0_4/SCL_15") (pintype "bidirectional"))
    )
    (net (code "120") (name "unconnected-(IC1-PIO0_5{slash}SDA-Pad16)") (class "Default")
      (node (ref "IC1") (pin "16") (pinfunction "PIO0_5/SDA_16") (pintype "bidirectional"))
    )
    (net (code "121") (name "unconnected-(IC1-PIO0_7{slash}~{CTS}-Pad23)") (class "Default")
      (node (ref "IC1") (pin "23") (pinfunction "PIO0_7/~{CTS}_23") (pintype "bidirectional"))
    )
    (net (code "122") (name "unconnected-(IC1-PIO0_11{slash}AD0{slash}CT32B0_MAT3-Pad32)") (class "Default")
      (node (ref "IC1") (pin "32") (pinfunction "PIO0_11/AD0/CT32B0_MAT3_32") (pintype "bidirectional"))
    )
    (net (code "123") (name "unconnected-(IC1-PIO1_5{slash}~{RTS}{slash}CT32B0_CAP0-Pad45)") (class "Default")
      (node (ref "IC1") (pin "45") (pinfunction "PIO1_5/~{RTS}/CT32B0_CAP0_45") (pintype "bidirectional"))
    )
    (net (code "124") (name "unconnected-(IC1-PIO1_6{slash}RXD{slash}CT32B0_MAT0-Pad46)") (class "Default")
      (node (ref "IC1") (pin "46") (pinfunction "PIO1_6/RXD/CT32B0_MAT0_46") (pintype "bidirectional"))
    )
    (net (code "125") (name "unconnected-(IC1-PIO1_7{slash}TXD{slash}CT32B0_MAT1-Pad47)") (class "Default")
      (node (ref "IC1") (pin "47") (pinfunction "PIO1_7/TXD/CT32B0_MAT1_47") (pintype "bidirectional"))
    )
    (net (code "126") (name "unconnected-(IC1-PIO1_8{slash}CT16B1_CAP0-Pad9)") (class "Default")
      (node (ref "IC1") (pin "9") (pinfunction "PIO1_8/CT16B1_CAP0_9") (pintype "bidirectional"))
    )
    (net (code "127") (name "unconnected-(IC1-PIO1_9{slash}CT16B1_MAT0-Pad17)") (class "Default")
      (node (ref "IC1") (pin "17") (pinfunction "PIO1_9/CT16B1_MAT0_17") (pintype "bidirectional"))
    )
    (net (code "128") (name "unconnected-(IC1-PIO2_4-Pad18)") (class "Default")
      (node (ref "IC1") (pin "18") (pinfunction "PIO2_4_18") (pintype "bidirectional"))
    )
    (net (code "129") (name "unconnected-(IC1-PIO2_5-Pad21)") (class "Default")
      (node (ref "IC1") (pin "21") (pinfunction "PIO2_5_21") (pintype "bidirectional"))
    )
    (net (code "130") (name "unconnected-(IC1-PIO2_6-Pad1)") (class "Default")
      (node (ref "IC1") (pin "1") (pinfunction "PIO2_6_1") (pintype "bidirectional"))
    )
    (net (code "131") (name "unconnected-(IC1-PIO2_7-Pad11)") (class "Default")
      (node (ref "IC1") (pin "11") (pinfunction "PIO2_7_11") (pintype "bidirectional"))
    )
    (net (code "132") (name "unconnected-(IC1-PIO2_8-Pad12)") (class "Default")
      (node (ref "IC1") (pin "12") (pinfunction "PIO2_8_12") (pintype "bidirectional"))
    )
    (net (code "133") (name "unconnected-(IC1-PIO2_11{slash}SCK0-Pad31)") (class "Default")
      (node (ref "IC1") (pin "31") (pinfunction "PIO2_11/SCK0_31") (pintype "bidirectional"))
    )
    (net (code "134") (name "unconnected-(IC1-PIO3_0{slash}~{DTR}-Pad36)") (class "Default")
      (node (ref "IC1") (pin "36") (pinfunction "PIO3_0/~{DTR}_36") (pintype "bidirectional"))
    )
    (net (code "135") (name "unconnected-(IC1-PIO3_1{slash}~{DSR}-Pad37)") (class "Default")
      (node (ref "IC1") (pin "37") (pinfunction "PIO3_1/~{DSR}_37") (pintype "bidirectional"))
    )
    (net (code "136") (name "unconnected-(IC1-PIO3_2{slash}~{DCD}-Pad43)") (class "Default")
      (node (ref "IC1") (pin "43") (pinfunction "PIO3_2/~{DCD}_43") (pintype "bidirectional"))
    )
    (net (code "137") (name "unconnected-(IC1-PIO3_3{slash}~{RI}-Pad48)") (class "Default")
      (node (ref "IC1") (pin "48") (pinfunction "PIO3_3/~{RI}_48") (pintype "bidirectional"))
    )
    (net (code "138") (name "unconnected-(IC5-VRF-Pad5)") (class "Default")
      (node (ref "IC5") (pin "5") (pinfunction "VRF_5") (pintype "bidirectional"))
    )
    (net (code "139") (name "~{RESET}") (class "Default")
      (node (ref "C34") (pin "1") (pinfunction "1_1") (pintype "passive"))
      (node (ref "IC1") (pin "3") (pinfunction "PIO0_0/~{RESET}_3") (pintype "bidirectional"))
      (node (ref "J1") (pin "1") (pinfunction "1_1") (pintype "passive"))
      (node (ref "R52") (pin "2") (pinfunction "2_2") (pintype "passive"))
    )
  )
)
